# NEOS_Master-Slave.net
KiCad netlist of a schematic drawn in Altium Designer
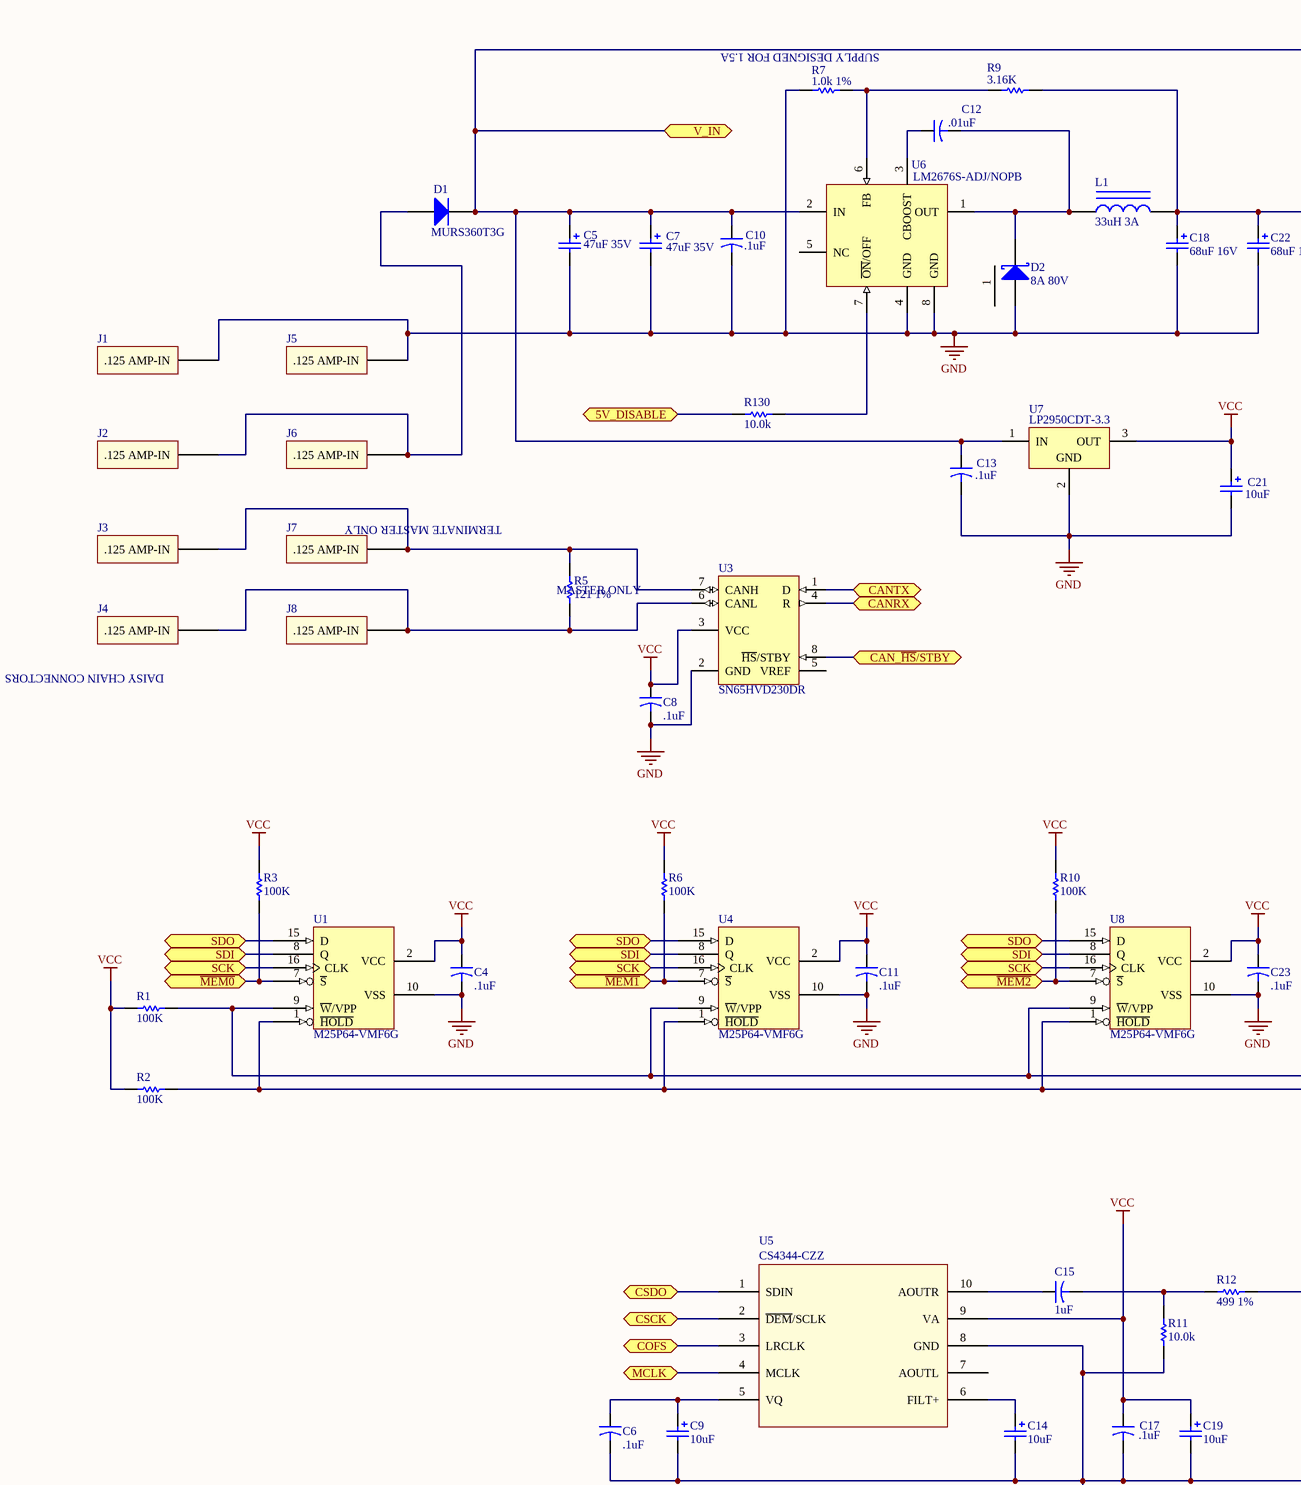
[diagram p0: NEOS Master-Slave.SchDoc, top left]
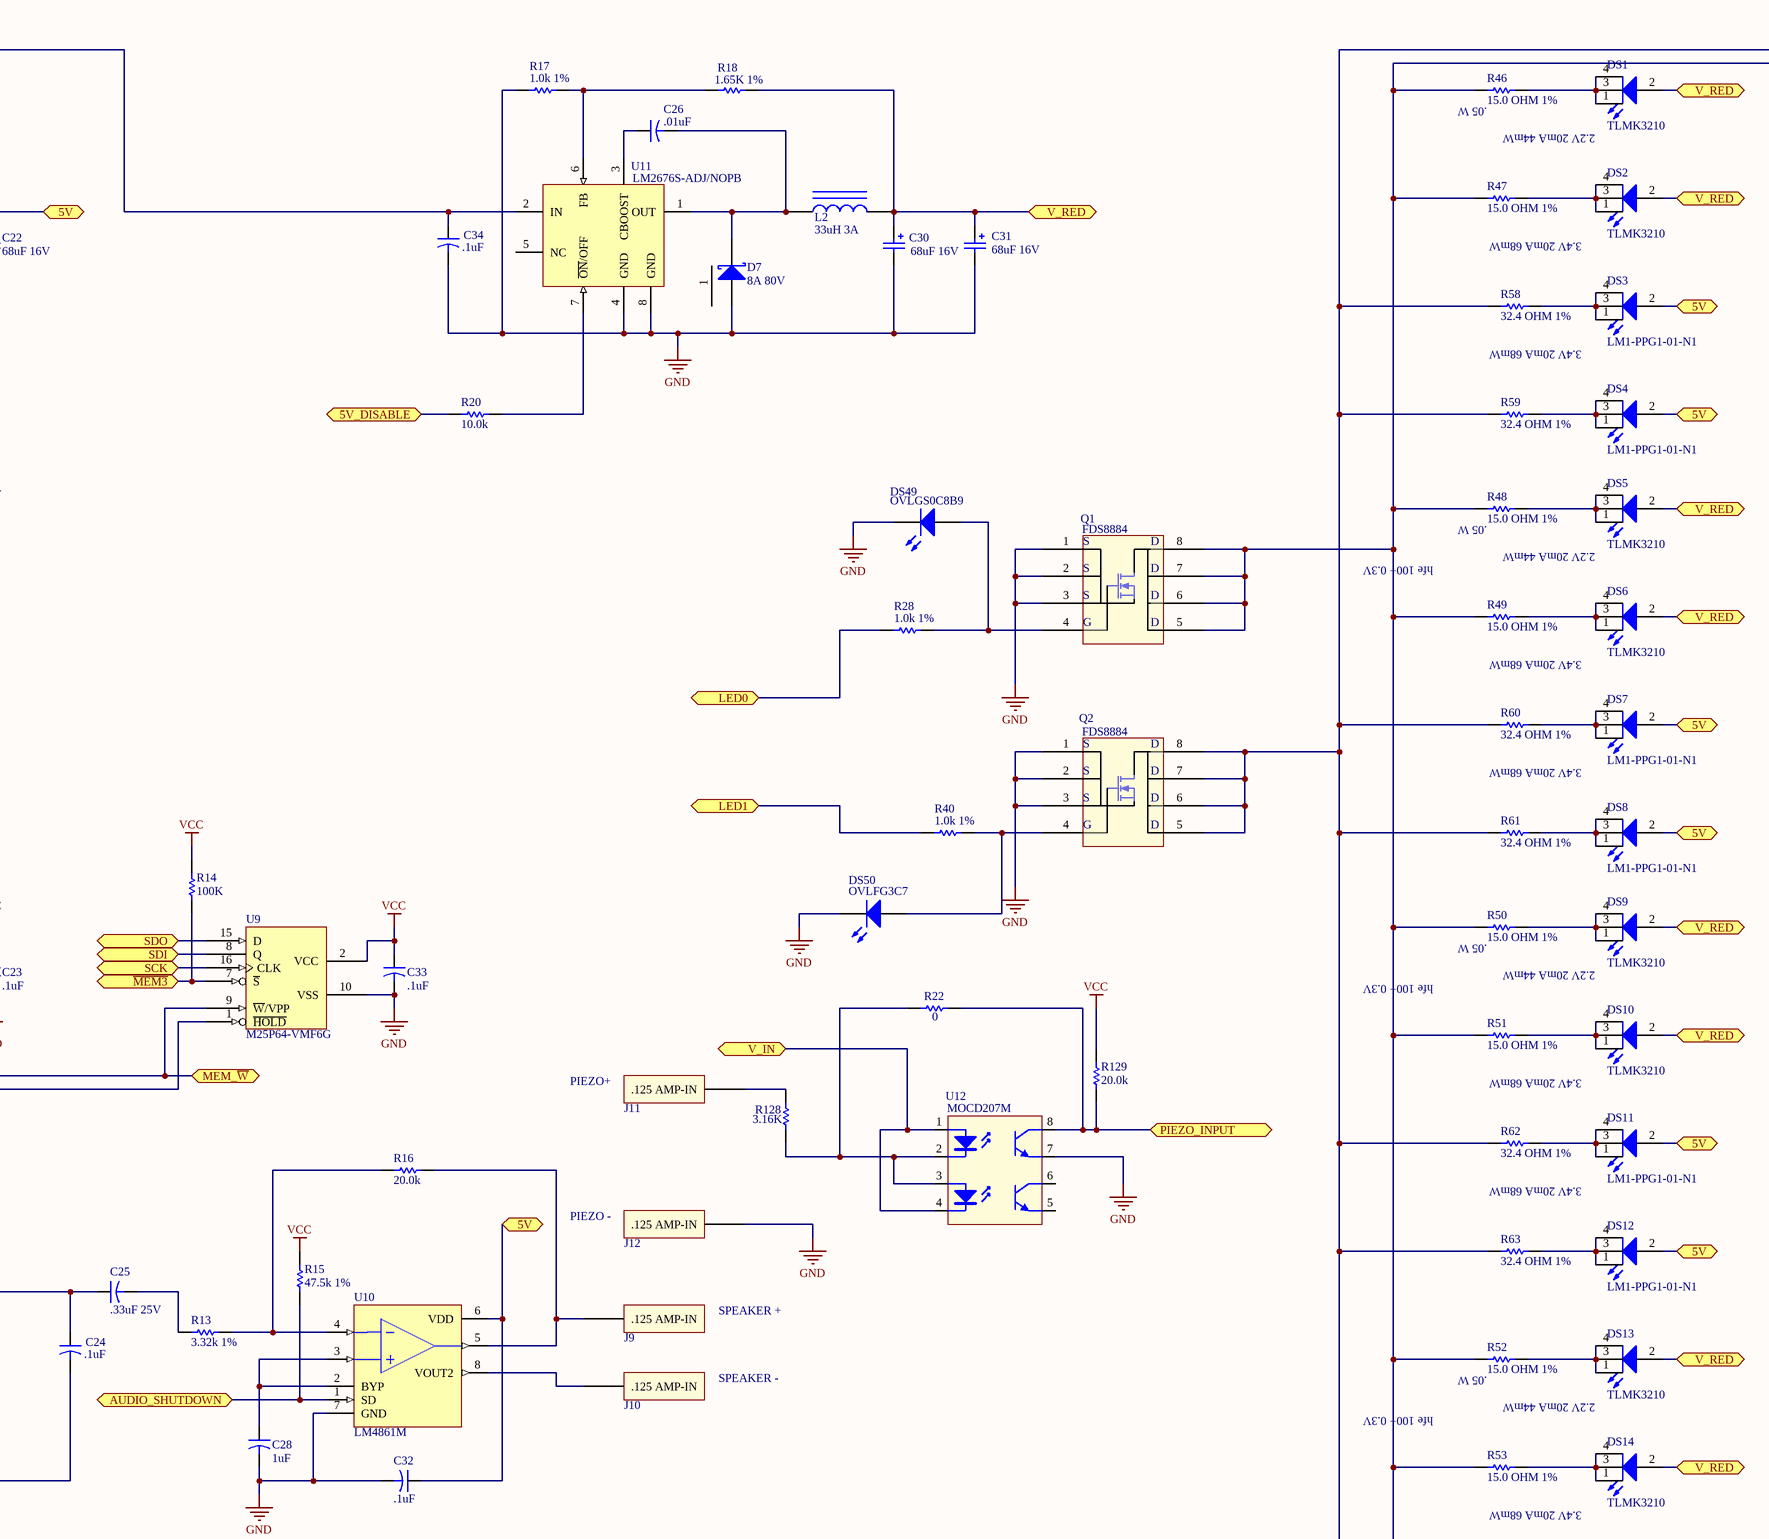
[diagram p1: NEOS Master-Slave.SchDoc, top middle]
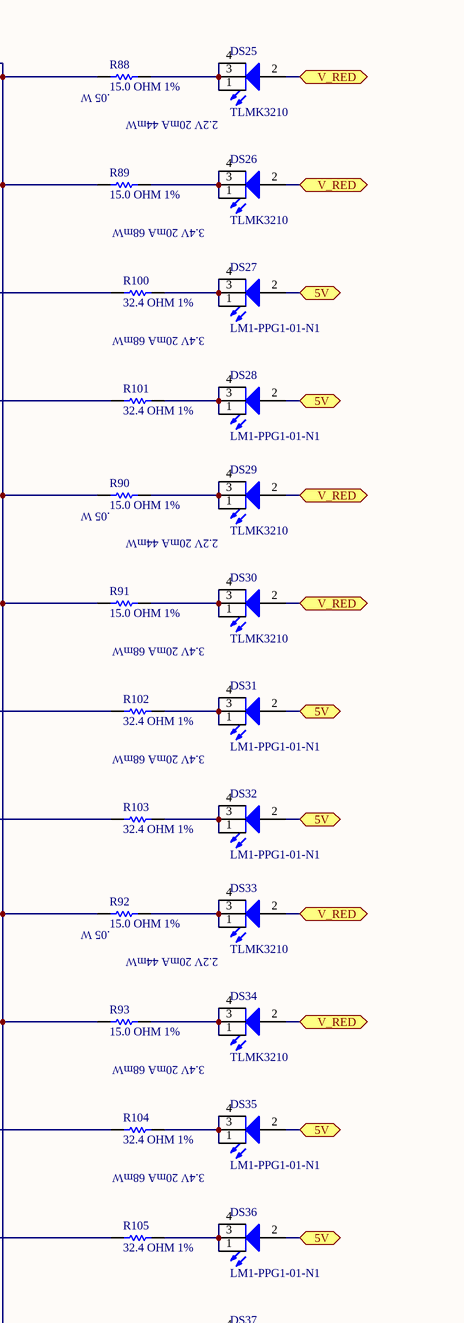
[diagram p2: NEOS Master-Slave.SchDoc, top right]
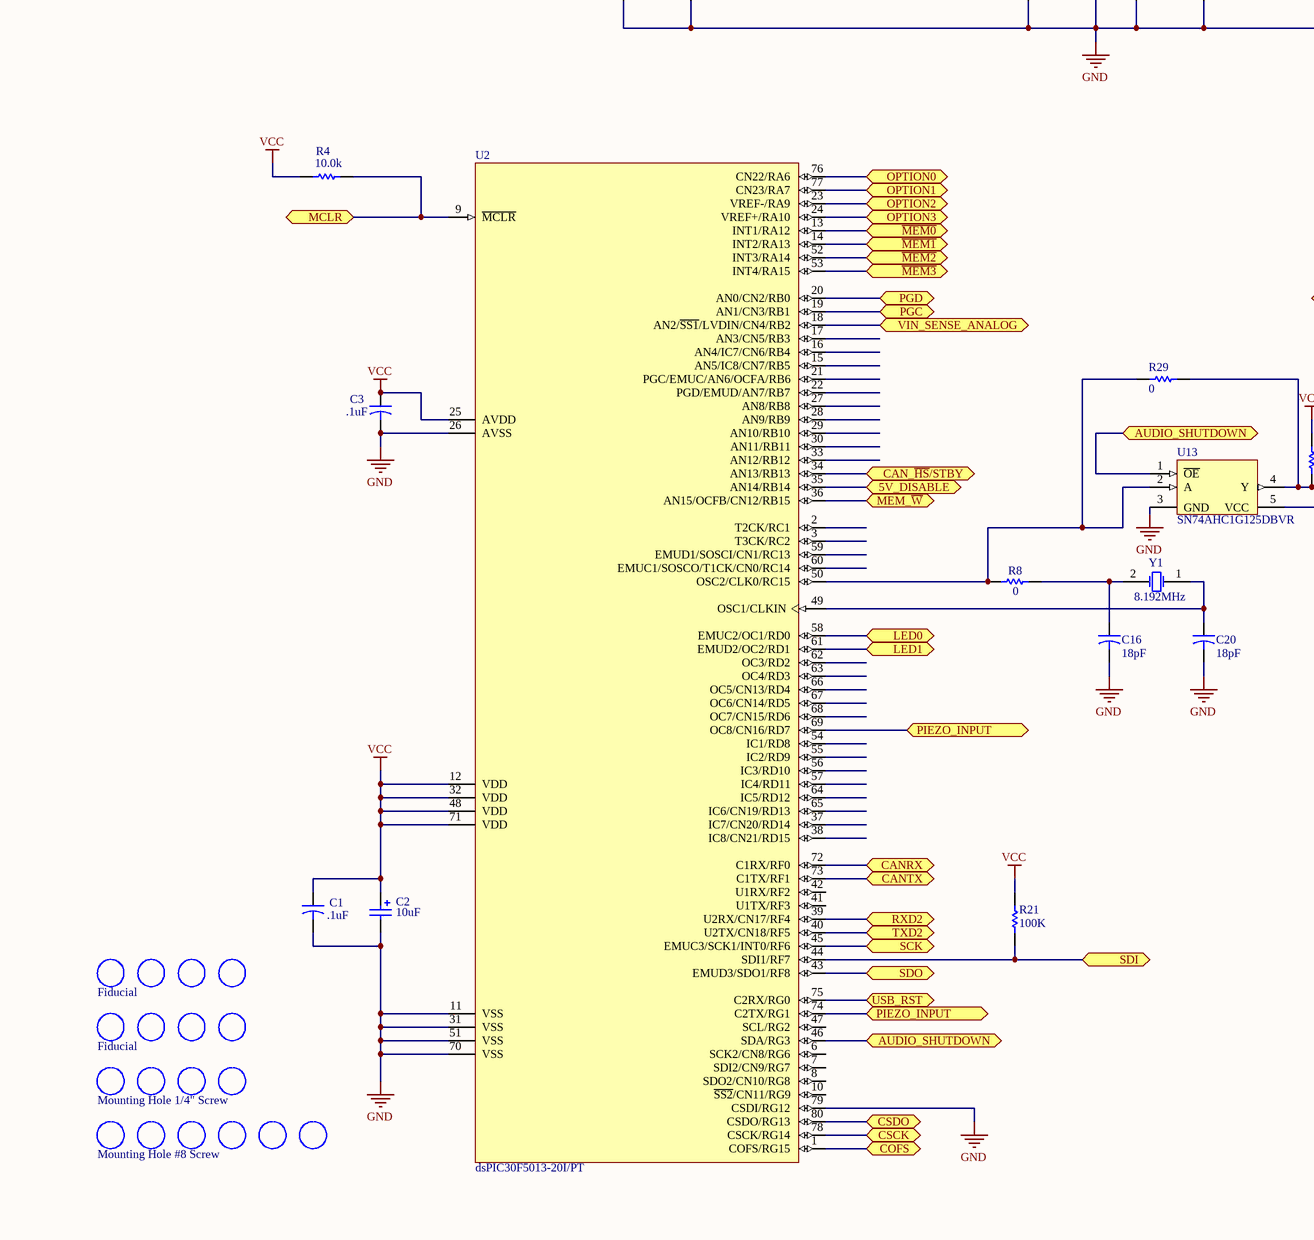
[diagram p3: NEOS Master-Slave.SchDoc, bottom left]
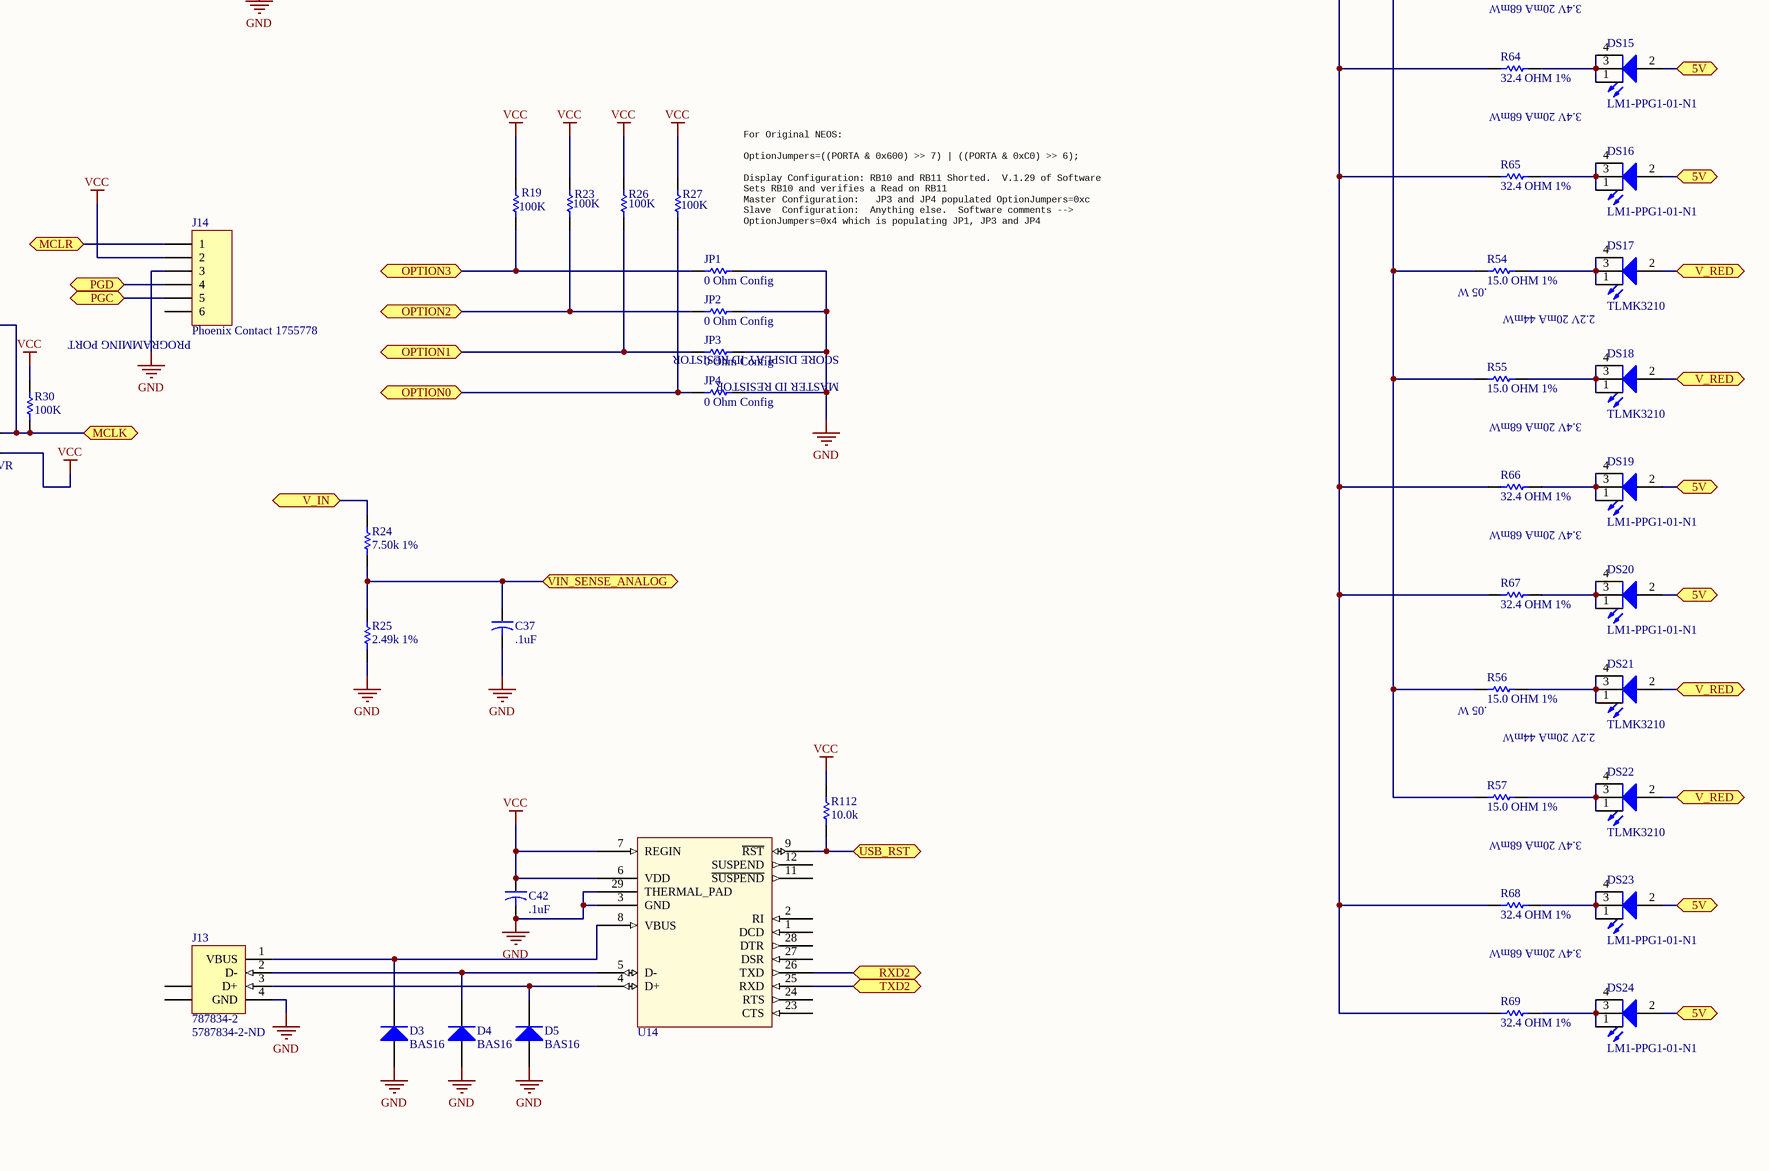
[diagram p4: NEOS Master-Slave.SchDoc, bottom middle]
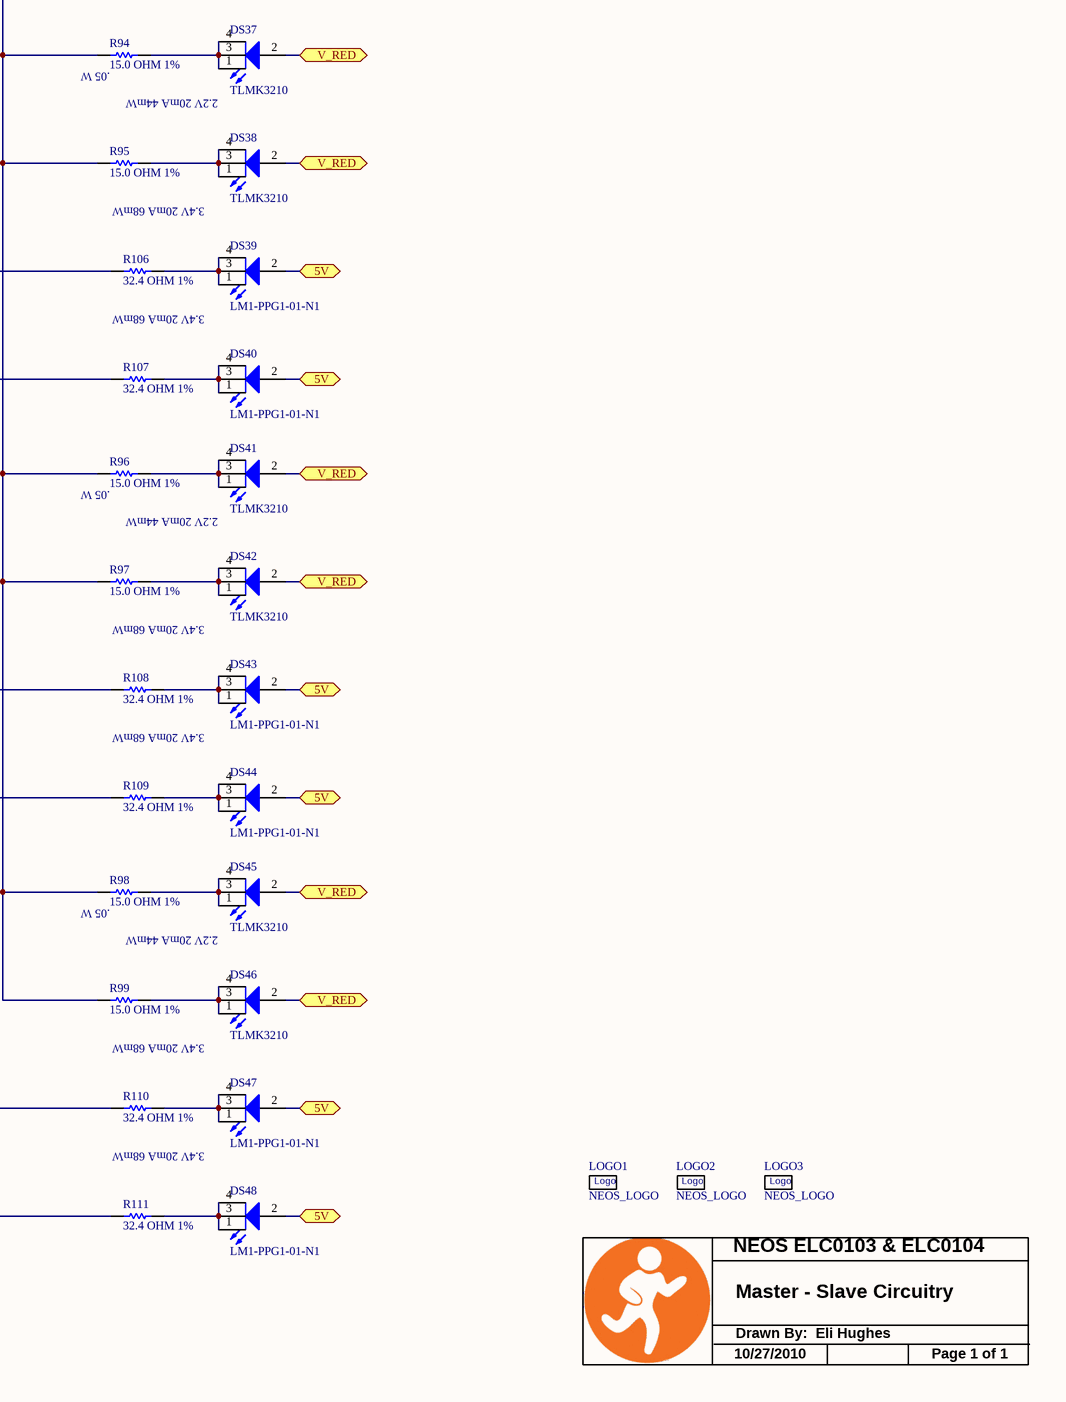
[diagram p5: NEOS Master-Slave.SchDoc, bottom right]

(export (version "E")
  (design (tool "Eeschema 10.0.6"))
  (components
    (comp (ref "C1")
      (value ".1uF")
      (footprint "C0805")
      (description "CAP .10UF 50V CERAMIC X7R 0805")
      (fields
        (field (name "MANUFACTURER") "Kemet")
        (field (name "MANUFACTURER PART NUMBER") "C0805C104K5RACTU")
      )
      (libsource (lib "API") (part "C#S/C0805C104K5RACK"))
    )
    (comp (ref "C2")
      (value "10uF")
      (footprint "API:C4X5.8")
      (description "CAP ELECT 10UF 16V FK SMD")
      (fields
        (field (name "MANUFACTURER") "Panasonic - ECG")
        (field (name "MANUFACTURER PART NUMBER") "EEE-FK1C100R")
      )
      (libsource (lib "API") (part "C#S/EEEFK1C100RP"))
    )
    (comp (ref "C3")
      (value ".1uF")
      (footprint "C0805")
      (description "CAP .10UF 50V CERAMIC X7R 0805")
      (fields
        (field (name "MANUFACTURER") "Kemet")
        (field (name "MANUFACTURER PART NUMBER") "C0805C104K5RACTU")
      )
      (libsource (lib "API") (part "C#S/C0805C104K5RACK"))
    )
    (comp (ref "C4")
      (value ".1uF")
      (footprint "C0805")
      (description "CAP .10UF 50V CERAMIC X7R 0805")
      (fields
        (field (name "MANUFACTURER") "Kemet")
        (field (name "MANUFACTURER PART NUMBER") "C0805C104K5RACTU")
      )
      (libsource (lib "") (part "C#S/C0805C104K5RACK_1"))
    )
    (comp (ref "C5")
      (value "47uF 35V")
      (footprint "C EIA7343-43 (X)")
      (description "CAPACITOR TANT 47UF 35V 10% SMD 7343-43 (EIA)")
      (fields
        (field (name "MANUFACTURER") "Kemet")
        (field (name "MANUFACTURER PART NUMBER") "T491X476K035AT")
      )
      (libsource (lib "API") (part "C#S/T491X476K035ATK"))
    )
    (comp (ref "C6")
      (value ".1uF")
      (footprint "C0805")
      (description "CAP .10UF 50V CERAMIC X7R 0805")
      (fields
        (field (name "MANUFACTURER") "Kemet")
        (field (name "MANUFACTURER PART NUMBER") "C0805C104K5RACTU")
      )
      (libsource (lib "") (part "C#S/C0805C104K5RACK_1"))
    )
    (comp (ref "C7")
      (value "47uF 35V")
      (footprint "C EIA7343-43 (X)")
      (description "CAPACITOR TANT 47UF 35V 10% SMD 7343-43 (EIA)")
      (fields
        (field (name "MANUFACTURER") "Kemet")
        (field (name "MANUFACTURER PART NUMBER") "T491X476K035AT")
      )
      (libsource (lib "API") (part "C#S/T491X476K035ATK"))
    )
    (comp (ref "C8")
      (value ".1uF")
      (footprint "C0805")
      (description "CAP .10UF 50V CERAMIC X7R 0805")
      (fields
        (field (name "MANUFACTURER") "Kemet")
        (field (name "MANUFACTURER PART NUMBER") "C0805C104K5RACTU")
      )
      (libsource (lib "") (part "C#S/C0805C104K5RACK_1"))
    )
    (comp (ref "C9")
      (value "10uF")
      (footprint "API:C4X5.8")
      (description "CAP ELECT 10UF 16V FK SMD")
      (fields
        (field (name "MANUFACTURER") "Panasonic - ECG")
        (field (name "MANUFACTURER PART NUMBER") "EEE-FK1C100R")
      )
      (libsource (lib "API") (part "C#S/EEEFK1C100RP"))
    )
    (comp (ref "C10")
      (value ".1uF")
      (footprint "C0805")
      (description "CAP .10UF 50V CERAMIC X7R 0805")
      (fields
        (field (name "MANUFACTURER") "Kemet")
        (field (name "MANUFACTURER PART NUMBER") "C0805C104K5RACTU")
      )
      (libsource (lib "") (part "C#S/C0805C104K5RACK_1"))
    )
    (comp (ref "C11")
      (value ".1uF")
      (footprint "C0805")
      (description "CAP .10UF 50V CERAMIC X7R 0805")
      (fields
        (field (name "MANUFACTURER") "Kemet")
        (field (name "MANUFACTURER PART NUMBER") "C0805C104K5RACTU")
      )
      (libsource (lib "") (part "C#S/C0805C104K5RACK_1"))
    )
    (comp (ref "C12")
      (value ".01uF")
      (footprint "API:C0805")
      (description "CAP 10000PF 50V CERAMIC X7R 0805")
      (fields
        (field (name "MANUFACTURER") "Kemet")
        (field (name "MANUFACTURER PART NUMBER") "C0805C103K5RACTU")
      )
      (libsource (lib "API") (part "C#S/C0805C103K5RAC"))
    )
    (comp (ref "C13")
      (value ".1uF")
      (footprint "C0805")
      (description "CAP .10UF 50V CERAMIC X7R 0805")
      (fields
        (field (name "MANUFACTURER") "Kemet")
        (field (name "MANUFACTURER PART NUMBER") "C0805C104K5RACTU")
      )
      (libsource (lib "") (part "C#S/C0805C104K5RACK_1"))
    )
    (comp (ref "C14")
      (value "10uF")
      (footprint "C4X5.8")
      (description "CAP ELECT 10UF 16V FK SMD")
      (fields
        (field (name "MANUFACTURER") "Panasonic - ECG")
        (field (name "MANUFACTURER PART NUMBER") "EEE-FK1C100R")
      )
      (libsource (lib "API") (part "C#S/EEEFK1C100RP"))
    )
    (comp (ref "C15")
      (value "1uF")
      (footprint "API:R1206")
      (description "CAP 1UF 25V CERAMIC X7R 1206")
      (fields
        (field (name "MANUFACTURER") "Panasonic - ECG")
        (field (name "MANUFACTURER PART NUMBER") "ECJ-3YB1E105K")
      )
      (libsource (lib "API") (part "C#S/ECJ3YB1E105KP"))
    )
    (comp (ref "C16")
      (value "18pF")
      (footprint "API:C0805")
      (description "CAP CERAMIC 18PF 50V NP0 0805")
      (fields
        (field (name "MANUFACTURER") "Kemet")
        (field (name "MANUFACTURER PART NUMBER") "C0805C180J5GACTU")
      )
      (libsource (lib "API") (part "C#S/C0805C180J5GACTUK"))
    )
    (comp (ref "C17")
      (value ".1uF")
      (footprint "C0805")
      (description "CAP .10UF 50V CERAMIC X7R 0805")
      (fields
        (field (name "MANUFACTURER") "Kemet")
        (field (name "MANUFACTURER PART NUMBER") "C0805C104K5RACTU")
      )
      (libsource (lib "") (part "C#S/C0805C104K5RACK_1"))
    )
    (comp (ref "C18")
      (value "68uF 16V")
      (footprint "API:C7343")
      (description "CAPACITOR TANT 68UF 16V 10% SMD")
      (fields
        (field (name "MANUFACTURER") "Kemet")
        (field (name "MANUFACTURER PART NUMBER") "T495D686K016ATE150")
      )
      (libsource (lib "API") (part "C#S/T495D686K016ATEK"))
    )
    (comp (ref "C19")
      (value "10uF")
      (footprint "API:C4X5.8")
      (description "CAP ELECT 10UF 16V FK SMD")
      (fields
        (field (name "MANUFACTURER") "Panasonic - ECG")
        (field (name "MANUFACTURER PART NUMBER") "EEE-FK1C100R")
      )
      (libsource (lib "API") (part "C#S/EEEFK1C100RP"))
    )
    (comp (ref "C20")
      (value "18pF")
      (footprint "API:C0805")
      (description "CAP CERAMIC 18PF 50V NP0 0805")
      (fields
        (field (name "MANUFACTURER") "Kemet")
        (field (name "MANUFACTURER PART NUMBER") "C0805C180J5GACTU")
      )
      (libsource (lib "API") (part "C#S/C0805C180J5GACTUK"))
    )
    (comp (ref "C21")
      (value "10uF")
      (footprint "API:C4X5.8")
      (description "CAP ELECT 10UF 16V FK SMD")
      (fields
        (field (name "MANUFACTURER") "Panasonic - ECG")
        (field (name "MANUFACTURER PART NUMBER") "EEE-FK1C100R")
      )
      (libsource (lib "API") (part "C#S/EEEFK1C100RP"))
    )
    (comp (ref "C22")
      (value "68uF 16V")
      (footprint "API:C7343")
      (description "CAPACITOR TANT 68UF 16V 10% SMD")
      (fields
        (field (name "MANUFACTURER") "Kemet")
        (field (name "MANUFACTURER PART NUMBER") "T495D686K016ATE150")
      )
      (libsource (lib "API") (part "C#S/T495D686K016ATEK"))
    )
    (comp (ref "C23")
      (value ".1uF")
      (footprint "C0805")
      (description "CAP .10UF 50V CERAMIC X7R 0805")
      (fields
        (field (name "MANUFACTURER") "Kemet")
        (field (name "MANUFACTURER PART NUMBER") "C0805C104K5RACTU")
      )
      (libsource (lib "") (part "C#S/C0805C104K5RACK_1"))
    )
    (comp (ref "C24")
      (value ".1uF")
      (footprint "C0805")
      (description "CAP .10UF 50V CERAMIC X7R 0805")
      (fields
        (field (name "MANUFACTURER") "Kemet")
        (field (name "MANUFACTURER PART NUMBER") "C0805C104K5RACTU")
      )
      (libsource (lib "") (part "C#S/C0805C104K5RACK_1"))
    )
    (comp (ref "C25")
      (value ".33uF 25V")
      (footprint "API:R1206")
      (description "CAP .33UF 25V CERAMIC X7R 1206")
      (fields
        (field (name "MANUFACTURER") "Panasonic - ECG")
        (field (name "MANUFACTURER PART NUMBER") "ECJ-3VB1E334K")
      )
      (libsource (lib "API") (part "C#S/ECJ3VB1E334KP"))
    )
    (comp (ref "C26")
      (value ".01uF")
      (footprint "API:C0805")
      (description "CAP 10000PF 50V CERAMIC X7R 0805")
      (fields
        (field (name "MANUFACTURER") "Kemet")
        (field (name "MANUFACTURER PART NUMBER") "C0805C103K5RACTU")
      )
      (libsource (lib "API") (part "C#S/C0805C103K5RAC"))
    )
    (comp (ref "C28")
      (value "1uF")
      (footprint "API:R1206")
      (description "CAP 1UF 25V CERAMIC X7R 1206")
      (fields
        (field (name "MANUFACTURER") "Panasonic - ECG")
        (field (name "MANUFACTURER PART NUMBER") "ECJ-3YB1E105K")
      )
      (libsource (lib "API") (part "C#S/ECJ3YB1E105KP"))
    )
    (comp (ref "C30")
      (value "68uF 16V")
      (footprint "C7343")
      (description "CAPACITOR TANT 68UF 16V 10% SMD")
      (fields
        (field (name "MANUFACTURER") "Kemet")
        (field (name "MANUFACTURER PART NUMBER") "T495D686K016ATE150")
      )
      (libsource (lib "API") (part "C#S/T495D686K016ATEK"))
    )
    (comp (ref "C31")
      (value "68uF 16V")
      (footprint "API:C7343")
      (description "CAPACITOR TANT 68UF 16V 10% SMD")
      (fields
        (field (name "MANUFACTURER") "Kemet")
        (field (name "MANUFACTURER PART NUMBER") "T495D686K016ATE150")
      )
      (libsource (lib "API") (part "C#S/T495D686K016ATEK"))
    )
    (comp (ref "C32")
      (value ".1uF")
      (footprint "C0805")
      (description "CAP .10UF 50V CERAMIC X7R 0805")
      (fields
        (field (name "MANUFACTURER") "Kemet")
        (field (name "MANUFACTURER PART NUMBER") "C0805C104K5RACTU")
      )
      (libsource (lib "") (part "C#S/C0805C104K5RACK_1"))
    )
    (comp (ref "C33")
      (value ".1uF")
      (footprint "C0805")
      (description "CAP .10UF 50V CERAMIC X7R 0805")
      (fields
        (field (name "MANUFACTURER") "Kemet")
        (field (name "MANUFACTURER PART NUMBER") "C0805C104K5RACTU")
      )
      (libsource (lib "") (part "C#S/C0805C104K5RACK_1"))
    )
    (comp (ref "C34")
      (value ".1uF")
      (footprint "C0805")
      (description "CAP .10UF 50V CERAMIC X7R 0805")
      (fields
        (field (name "MANUFACTURER") "Kemet")
        (field (name "MANUFACTURER PART NUMBER") "C0805C104K5RACTU")
      )
      (libsource (lib "") (part "C#S/C0805C104K5RACK_1"))
    )
    (comp (ref "C37")
      (value ".1uF")
      (footprint "C0805")
      (description "CAP .10UF 50V CERAMIC X7R 0805")
      (fields
        (field (name "MANUFACTURER") "Kemet")
        (field (name "MANUFACTURER PART NUMBER") "C0805C104K5RACTU")
      )
      (libsource (lib "") (part "C#S/C0805C104K5RACK_1"))
    )
    (comp (ref "C42")
      (value ".1uF")
      (footprint "C0805")
      (description "CAP .10UF 50V CERAMIC X7R 0805")
      (fields
        (field (name "MANUFACTURER") "Kemet")
        (field (name "MANUFACTURER PART NUMBER") "C0805C104K5RACTU")
      )
      (libsource (lib "") (part "C#S/C0805C104K5RACK_1"))
    )
    (comp (ref "D1")
      (value "DIODE ULTRA FAST 3A 600V SMC")
      (footprint "API:DIODE_SMC")
      (fields
        (field (name "MANUFACTURER") "ON Semiconductor")
        (field (name "MANUFACTURER PART NUMBER") "MURS360T3G")
      )
      (libsource (lib "API") (part "D#S/MURS360T3GM"))
    )
    (comp (ref "D2")
      (value "8A 80V")
      (footprint "API:D2PAK")
      (description "DIODE SCHOTTKY 80V 8A D2PAK")
      (fields
        (field (name "MANUFACTURER") "Vishay IR")
        (field (name "MANUFACTURER PART NUMBER") "8TQ100SPBF")
      )
      (libsource (lib "API") (part "D#S/8TQ080SPBFZ"))
    )
    (comp (ref "D3")
      (value "BAS16")
      (footprint "API:SOT23")
      (description "Diodes Inc BAS16 75V 200mA")
      (fields
        (field (name "MANUFACTURER") "Diodes Inc")
        (field (name "MANUFACTURER PART NUMBER") "BAS16-7-F")
      )
      (libsource (lib "API") (part "D#S/BAS167F0D"))
    )
    (comp (ref "D4")
      (value "BAS16")
      (footprint "API:SOT23")
      (description "Diodes Inc BAS16 75V 200mA")
      (fields
        (field (name "MANUFACTURER") "Diodes Inc")
        (field (name "MANUFACTURER PART NUMBER") "BAS16-7-F")
      )
      (libsource (lib "API") (part "D#S/BAS167F0D"))
    )
    (comp (ref "D5")
      (value "BAS16")
      (footprint "API:SOT23")
      (description "Diodes Inc BAS16 75V 200mA")
      (fields
        (field (name "MANUFACTURER") "Diodes Inc")
        (field (name "MANUFACTURER PART NUMBER") "BAS16-7-F")
      )
      (libsource (lib "API") (part "D#S/BAS167F0D"))
    )
    (comp (ref "D7")
      (value "8A 80V")
      (footprint "API:D2PAK")
      (description "DIODE SCHOTTKY 80V 8A D2PAK")
      (fields
        (field (name "MANUFACTURER") "Vishay IR")
        (field (name "MANUFACTURER PART NUMBER") "8TQ100SPBF")
      )
      (libsource (lib "API") (part "D#S/8TQ080SPBFZ"))
    )
    (comp (ref "DS1")
      (value "TLMK3210")
      (footprint "API:L#S/TLMK3210Z")
      (description "Vishay Red LED PLCC-3")
      (fields
        (field (name "MANUFACTURER") "Vishay")
        (field (name "MANUFACTURER PART NUMBER") "TLMK3210-GS08")
      )
      (libsource (lib "API") (part "L#S/TLMK3210"))
    )
    (comp (ref "DS2")
      (value "TLMK3210")
      (footprint "API:L#S/TLMK3210Z")
      (description "Vishay Red LED PLCC-3")
      (fields
        (field (name "MANUFACTURER") "Vishay")
        (field (name "MANUFACTURER PART NUMBER") "TLMK3210-GS08")
      )
      (libsource (lib "API") (part "L#S/TLMK3210"))
    )
    (comp (ref "DS3")
      (value "LM1-PPG1-01-N1")
      (footprint "L#S/TLMK3210Z")
      (description "120-degree, 3.3 x 3.5-mm, SMT LED in green color with water-transparent lens")
      (fields (field (name "MANUFACTURER") "Cree"))
      (libsource (lib "API") (part "L#S/LM1PPG103N1Z"))
    )
    (comp (ref "DS4")
      (value "LM1-PPG1-01-N1")
      (footprint "L#S/TLMK3210Z")
      (description "120-degree, 3.3 x 3.5-mm, SMT LED in green color with water-transparent lens")
      (fields (field (name "MANUFACTURER") "Cree"))
      (libsource (lib "API") (part "L#S/LM1PPG103N1Z"))
    )
    (comp (ref "DS5")
      (value "TLMK3210")
      (footprint "API:L#S/TLMK3210Z")
      (description "Vishay Red LED PLCC-3")
      (fields
        (field (name "MANUFACTURER") "Vishay")
        (field (name "MANUFACTURER PART NUMBER") "TLMK3210-GS08")
      )
      (libsource (lib "API") (part "L#S/TLMK3210"))
    )
    (comp (ref "DS6")
      (value "TLMK3210")
      (footprint "API:L#S/TLMK3210Z")
      (description "Vishay Red LED PLCC-3")
      (fields
        (field (name "MANUFACTURER") "Vishay")
        (field (name "MANUFACTURER PART NUMBER") "TLMK3210-GS08")
      )
      (libsource (lib "API") (part "L#S/TLMK3210"))
    )
    (comp (ref "DS7")
      (value "LM1-PPG1-01-N1")
      (footprint "L#S/TLMK3210Z")
      (description "120-degree, 3.3 x 3.5-mm, SMT LED in green color with water-transparent lens")
      (fields (field (name "MANUFACTURER") "Cree"))
      (libsource (lib "API") (part "L#S/LM1PPG103N1Z"))
    )
    (comp (ref "DS8")
      (value "LM1-PPG1-01-N1")
      (footprint "L#S/TLMK3210Z")
      (description "120-degree, 3.3 x 3.5-mm, SMT LED in green color with water-transparent lens")
      (fields (field (name "MANUFACTURER") "Cree"))
      (libsource (lib "API") (part "L#S/LM1PPG103N1Z"))
    )
    (comp (ref "DS9")
      (value "TLMK3210")
      (footprint "API:L#S/TLMK3210Z")
      (description "Vishay Red LED PLCC-3")
      (fields
        (field (name "MANUFACTURER") "Vishay")
        (field (name "MANUFACTURER PART NUMBER") "TLMK3210-GS08")
      )
      (libsource (lib "API") (part "L#S/TLMK3210"))
    )
    (comp (ref "DS10")
      (value "TLMK3210")
      (footprint "API:L#S/TLMK3210Z")
      (description "Vishay Red LED PLCC-3")
      (fields
        (field (name "MANUFACTURER") "Vishay")
        (field (name "MANUFACTURER PART NUMBER") "TLMK3210-GS08")
      )
      (libsource (lib "API") (part "L#S/TLMK3210"))
    )
    (comp (ref "DS11")
      (value "LM1-PPG1-01-N1")
      (footprint "L#S/TLMK3210Z")
      (description "120-degree, 3.3 x 3.5-mm, SMT LED in green color with water-transparent lens")
      (fields (field (name "MANUFACTURER") "Cree"))
      (libsource (lib "API") (part "L#S/LM1PPG103N1Z"))
    )
    (comp (ref "DS12")
      (value "LM1-PPG1-01-N1")
      (footprint "L#S/TLMK3210Z")
      (description "120-degree, 3.3 x 3.5-mm, SMT LED in green color with water-transparent lens")
      (fields (field (name "MANUFACTURER") "Cree"))
      (libsource (lib "API") (part "L#S/LM1PPG103N1Z"))
    )
    (comp (ref "DS13")
      (value "TLMK3210")
      (footprint "API:L#S/TLMK3210Z")
      (description "Vishay Red LED PLCC-3")
      (fields
        (field (name "MANUFACTURER") "Vishay")
        (field (name "MANUFACTURER PART NUMBER") "TLMK3210-GS08")
      )
      (libsource (lib "API") (part "L#S/TLMK3210"))
    )
    (comp (ref "DS14")
      (value "TLMK3210")
      (footprint "API:L#S/TLMK3210Z")
      (description "Vishay Red LED PLCC-3")
      (fields
        (field (name "MANUFACTURER") "Vishay")
        (field (name "MANUFACTURER PART NUMBER") "TLMK3210-GS08")
      )
      (libsource (lib "API") (part "L#S/TLMK3210"))
    )
    (comp (ref "DS15")
      (value "LM1-PPG1-01-N1")
      (footprint "L#S/TLMK3210Z")
      (description "120-degree, 3.3 x 3.5-mm, SMT LED in green color with water-transparent lens")
      (fields (field (name "MANUFACTURER") "Cree"))
      (libsource (lib "API") (part "L#S/LM1PPG103N1Z"))
    )
    (comp (ref "DS16")
      (value "LM1-PPG1-01-N1")
      (footprint "L#S/TLMK3210Z")
      (description "120-degree, 3.3 x 3.5-mm, SMT LED in green color with water-transparent lens")
      (fields (field (name "MANUFACTURER") "Cree"))
      (libsource (lib "API") (part "L#S/LM1PPG103N1Z"))
    )
    (comp (ref "DS17")
      (value "TLMK3210")
      (footprint "API:L#S/TLMK3210Z")
      (description "Vishay Red LED PLCC-3")
      (fields
        (field (name "MANUFACTURER") "Vishay")
        (field (name "MANUFACTURER PART NUMBER") "TLMK3210-GS08")
      )
      (libsource (lib "API") (part "L#S/TLMK3210"))
    )
    (comp (ref "DS18")
      (value "TLMK3210")
      (footprint "API:L#S/TLMK3210Z")
      (description "Vishay Red LED PLCC-3")
      (fields
        (field (name "MANUFACTURER") "Vishay")
        (field (name "MANUFACTURER PART NUMBER") "TLMK3210-GS08")
      )
      (libsource (lib "API") (part "L#S/TLMK3210"))
    )
    (comp (ref "DS19")
      (value "LM1-PPG1-01-N1")
      (footprint "L#S/TLMK3210Z")
      (description "120-degree, 3.3 x 3.5-mm, SMT LED in green color with water-transparent lens")
      (fields (field (name "MANUFACTURER") "Cree"))
      (libsource (lib "API") (part "L#S/LM1PPG103N1Z"))
    )
    (comp (ref "DS20")
      (value "LM1-PPG1-01-N1")
      (footprint "L#S/TLMK3210Z")
      (description "120-degree, 3.3 x 3.5-mm, SMT LED in green color with water-transparent lens")
      (fields (field (name "MANUFACTURER") "Cree"))
      (libsource (lib "API") (part "L#S/LM1PPG103N1Z"))
    )
    (comp (ref "DS21")
      (value "TLMK3210")
      (footprint "API:L#S/TLMK3210Z")
      (description "Vishay Red LED PLCC-3")
      (fields
        (field (name "MANUFACTURER") "Vishay")
        (field (name "MANUFACTURER PART NUMBER") "TLMK3210-GS08")
      )
      (libsource (lib "API") (part "L#S/TLMK3210"))
    )
    (comp (ref "DS22")
      (value "TLMK3210")
      (footprint "API:L#S/TLMK3210Z")
      (description "Vishay Red LED PLCC-3")
      (fields
        (field (name "MANUFACTURER") "Vishay")
        (field (name "MANUFACTURER PART NUMBER") "TLMK3210-GS08")
      )
      (libsource (lib "API") (part "L#S/TLMK3210"))
    )
    (comp (ref "DS23")
      (value "LM1-PPG1-01-N1")
      (footprint "L#S/TLMK3210Z")
      (description "120-degree, 3.3 x 3.5-mm, SMT LED in green color with water-transparent lens")
      (fields (field (name "MANUFACTURER") "Cree"))
      (libsource (lib "API") (part "L#S/LM1PPG103N1Z"))
    )
    (comp (ref "DS24")
      (value "LM1-PPG1-01-N1")
      (footprint "L#S/TLMK3210Z")
      (description "120-degree, 3.3 x 3.5-mm, SMT LED in green color with water-transparent lens")
      (fields (field (name "MANUFACTURER") "Cree"))
      (libsource (lib "API") (part "L#S/LM1PPG103N1Z"))
    )
    (comp (ref "DS25")
      (value "TLMK3210")
      (footprint "API:L#S/TLMK3210Z")
      (description "Vishay Red LED PLCC-3")
      (fields
        (field (name "MANUFACTURER") "Vishay")
        (field (name "MANUFACTURER PART NUMBER") "TLMK3210-GS08")
      )
      (libsource (lib "API") (part "L#S/TLMK3210"))
    )
    (comp (ref "DS26")
      (value "TLMK3210")
      (footprint "API:L#S/TLMK3210Z")
      (description "Vishay Red LED PLCC-3")
      (fields
        (field (name "MANUFACTURER") "Vishay")
        (field (name "MANUFACTURER PART NUMBER") "TLMK3210-GS08")
      )
      (libsource (lib "API") (part "L#S/TLMK3210"))
    )
    (comp (ref "DS27")
      (value "LM1-PPG1-01-N1")
      (footprint "L#S/TLMK3210Z")
      (description "120-degree, 3.3 x 3.5-mm, SMT LED in green color with water-transparent lens")
      (fields (field (name "MANUFACTURER") "Cree"))
      (libsource (lib "API") (part "L#S/LM1PPG103N1Z"))
    )
    (comp (ref "DS28")
      (value "LM1-PPG1-01-N1")
      (footprint "L#S/TLMK3210Z")
      (description "120-degree, 3.3 x 3.5-mm, SMT LED in green color with water-transparent lens")
      (fields (field (name "MANUFACTURER") "Cree"))
      (libsource (lib "API") (part "L#S/LM1PPG103N1Z"))
    )
    (comp (ref "DS29")
      (value "TLMK3210")
      (footprint "API:L#S/TLMK3210Z")
      (description "Vishay Red LED PLCC-3")
      (fields
        (field (name "MANUFACTURER") "Vishay")
        (field (name "MANUFACTURER PART NUMBER") "TLMK3210-GS08")
      )
      (libsource (lib "API") (part "L#S/TLMK3210"))
    )
    (comp (ref "DS30")
      (value "TLMK3210")
      (footprint "API:L#S/TLMK3210Z")
      (description "Vishay Red LED PLCC-3")
      (fields
        (field (name "MANUFACTURER") "Vishay")
        (field (name "MANUFACTURER PART NUMBER") "TLMK3210-GS08")
      )
      (libsource (lib "API") (part "L#S/TLMK3210"))
    )
    (comp (ref "DS31")
      (value "LM1-PPG1-01-N1")
      (footprint "L#S/TLMK3210Z")
      (description "120-degree, 3.3 x 3.5-mm, SMT LED in green color with water-transparent lens")
      (fields (field (name "MANUFACTURER") "Cree"))
      (libsource (lib "API") (part "L#S/LM1PPG103N1Z"))
    )
    (comp (ref "DS32")
      (value "LM1-PPG1-01-N1")
      (footprint "L#S/TLMK3210Z")
      (description "120-degree, 3.3 x 3.5-mm, SMT LED in green color with water-transparent lens")
      (fields (field (name "MANUFACTURER") "Cree"))
      (libsource (lib "API") (part "L#S/LM1PPG103N1Z"))
    )
    (comp (ref "DS33")
      (value "TLMK3210")
      (footprint "API:L#S/TLMK3210Z")
      (description "Vishay Red LED PLCC-3")
      (fields
        (field (name "MANUFACTURER") "Vishay")
        (field (name "MANUFACTURER PART NUMBER") "TLMK3210-GS08")
      )
      (libsource (lib "API") (part "L#S/TLMK3210"))
    )
    (comp (ref "DS34")
      (value "TLMK3210")
      (footprint "API:L#S/TLMK3210Z")
      (description "Vishay Red LED PLCC-3")
      (fields
        (field (name "MANUFACTURER") "Vishay")
        (field (name "MANUFACTURER PART NUMBER") "TLMK3210-GS08")
      )
      (libsource (lib "API") (part "L#S/TLMK3210"))
    )
    (comp (ref "DS35")
      (value "LM1-PPG1-01-N1")
      (footprint "L#S/TLMK3210Z")
      (description "120-degree, 3.3 x 3.5-mm, SMT LED in green color with water-transparent lens")
      (fields (field (name "MANUFACTURER") "Cree"))
      (libsource (lib "API") (part "L#S/LM1PPG103N1Z"))
    )
    (comp (ref "DS36")
      (value "LM1-PPG1-01-N1")
      (footprint "L#S/TLMK3210Z")
      (description "120-degree, 3.3 x 3.5-mm, SMT LED in green color with water-transparent lens")
      (fields (field (name "MANUFACTURER") "Cree"))
      (libsource (lib "API") (part "L#S/LM1PPG103N1Z"))
    )
    (comp (ref "DS37")
      (value "TLMK3210")
      (footprint "API:L#S/TLMK3210Z")
      (description "Vishay Red LED PLCC-3")
      (fields
        (field (name "MANUFACTURER") "Vishay")
        (field (name "MANUFACTURER PART NUMBER") "TLMK3210-GS08")
      )
      (libsource (lib "API") (part "L#S/TLMK3210"))
    )
    (comp (ref "DS38")
      (value "TLMK3210")
      (footprint "API:L#S/TLMK3210Z")
      (description "Vishay Red LED PLCC-3")
      (fields
        (field (name "MANUFACTURER") "Vishay")
        (field (name "MANUFACTURER PART NUMBER") "TLMK3210-GS08")
      )
      (libsource (lib "API") (part "L#S/TLMK3210"))
    )
    (comp (ref "DS39")
      (value "LM1-PPG1-01-N1")
      (footprint "L#S/TLMK3210Z")
      (description "120-degree, 3.3 x 3.5-mm, SMT LED in green color with water-transparent lens")
      (fields (field (name "MANUFACTURER") "Cree"))
      (libsource (lib "API") (part "L#S/LM1PPG103N1Z"))
    )
    (comp (ref "DS40")
      (value "LM1-PPG1-01-N1")
      (footprint "L#S/TLMK3210Z")
      (description "120-degree, 3.3 x 3.5-mm, SMT LED in green color with water-transparent lens")
      (fields (field (name "MANUFACTURER") "Cree"))
      (libsource (lib "API") (part "L#S/LM1PPG103N1Z"))
    )
    (comp (ref "DS41")
      (value "TLMK3210")
      (footprint "API:L#S/TLMK3210Z")
      (description "Vishay Red LED PLCC-3")
      (fields
        (field (name "MANUFACTURER") "Vishay")
        (field (name "MANUFACTURER PART NUMBER") "TLMK3210-GS08")
      )
      (libsource (lib "API") (part "L#S/TLMK3210"))
    )
    (comp (ref "DS42")
      (value "TLMK3210")
      (footprint "API:L#S/TLMK3210Z")
      (description "Vishay Red LED PLCC-3")
      (fields
        (field (name "MANUFACTURER") "Vishay")
        (field (name "MANUFACTURER PART NUMBER") "TLMK3210-GS08")
      )
      (libsource (lib "API") (part "L#S/TLMK3210"))
    )
    (comp (ref "DS43")
      (value "LM1-PPG1-01-N1")
      (footprint "L#S/TLMK3210Z")
      (description "120-degree, 3.3 x 3.5-mm, SMT LED in green color with water-transparent lens")
      (fields (field (name "MANUFACTURER") "Cree"))
      (libsource (lib "API") (part "L#S/LM1PPG103N1Z"))
    )
    (comp (ref "DS44")
      (value "LM1-PPG1-01-N1")
      (footprint "L#S/TLMK3210Z")
      (description "120-degree, 3.3 x 3.5-mm, SMT LED in green color with water-transparent lens")
      (fields (field (name "MANUFACTURER") "Cree"))
      (libsource (lib "API") (part "L#S/LM1PPG103N1Z"))
    )
    (comp (ref "DS45")
      (value "TLMK3210")
      (footprint "API:L#S/TLMK3210Z")
      (description "Vishay Red LED PLCC-3")
      (fields
        (field (name "MANUFACTURER") "Vishay")
        (field (name "MANUFACTURER PART NUMBER") "TLMK3210-GS08")
      )
      (libsource (lib "API") (part "L#S/TLMK3210"))
    )
    (comp (ref "DS46")
      (value "TLMK3210")
      (footprint "API:L#S/TLMK3210Z")
      (description "Vishay Red LED PLCC-3")
      (fields
        (field (name "MANUFACTURER") "Vishay")
        (field (name "MANUFACTURER PART NUMBER") "TLMK3210-GS08")
      )
      (libsource (lib "API") (part "L#S/TLMK3210"))
    )
    (comp (ref "DS47")
      (value "LM1-PPG1-01-N1")
      (footprint "L#S/TLMK3210Z")
      (description "120-degree, 3.3 x 3.5-mm, SMT LED in green color with water-transparent lens")
      (fields (field (name "MANUFACTURER") "Cree"))
      (libsource (lib "API") (part "L#S/LM1PPG103N1Z"))
    )
    (comp (ref "DS48")
      (value "LM1-PPG1-01-N1")
      (footprint "L#S/TLMK3210Z")
      (description "120-degree, 3.3 x 3.5-mm, SMT LED in green color with water-transparent lens")
      (fields (field (name "MANUFACTURER") "Cree"))
      (libsource (lib "API") (part "L#S/LM1PPG103N1Z"))
    )
    (comp (ref "DS49")
      (value "OVLGS0C8B9")
      (footprint "LED T1-3/4 Flush")
      (description "LED 631NM TAPERED RED 5MM")
      (fields (field (name "MANUFACTURER") "TT Electronics/Optek Technology"))
      (libsource (lib "API") (part "LRCOVLFR3C7Z"))
    )
    (comp (ref "DS50")
      (value "OVLFG3C7")
      (footprint "LED T1-3/4 Flush")
      (description "LED 525NM ROUND GREEN 5MM")
      (fields (field (name "MANUFACTURER") "TT Electronics/Optek Technology"))
      (libsource (lib "API") (part "LGCOVLFG3C7Z"))
    )
    (comp (ref "FID1")
      (value "Fiducial")
      (footprint "Fiducial")
      (fields
        (field (name "MANUFACTURER") "Manufacturer")
        (field (name "MANUFACTURER PART NUMBER") "Manufacturer Part Number")
      )
      (libsource (lib "API") (part "Fiducial"))
    )
    (comp (ref "FID2")
      (value "Fiducial")
      (footprint "Fiducial")
      (fields
        (field (name "MANUFACTURER") "Manufacturer")
        (field (name "MANUFACTURER PART NUMBER") "Manufacturer Part Number")
      )
      (libsource (lib "API") (part "Fiducial"))
    )
    (comp (ref "FID3")
      (value "Fiducial")
      (footprint "Fiducial")
      (fields
        (field (name "MANUFACTURER") "Manufacturer")
        (field (name "MANUFACTURER PART NUMBER") "Manufacturer Part Number")
      )
      (libsource (lib "API") (part "Fiducial"))
    )
    (comp (ref "FID4")
      (value "Fiducial")
      (footprint "Fiducial")
      (fields
        (field (name "MANUFACTURER") "Manufacturer")
        (field (name "MANUFACTURER PART NUMBER") "Manufacturer Part Number")
      )
      (libsource (lib "API") (part "Fiducial"))
    )
    (comp (ref "FID5")
      (value "Fiducial")
      (footprint "Fiducial")
      (fields
        (field (name "MANUFACTURER") "Manufacturer")
        (field (name "MANUFACTURER PART NUMBER") "Manufacturer Part Number")
      )
      (libsource (lib "API") (part "Fiducial"))
    )
    (comp (ref "FID6")
      (value "Fiducial")
      (footprint "Fiducial")
      (fields
        (field (name "MANUFACTURER") "Manufacturer")
        (field (name "MANUFACTURER PART NUMBER") "Manufacturer Part Number")
      )
      (libsource (lib "API") (part "Fiducial"))
    )
    (comp (ref "FID7")
      (value "Fiducial")
      (footprint "Fiducial")
      (fields
        (field (name "MANUFACTURER") "Manufacturer")
        (field (name "MANUFACTURER PART NUMBER") "Manufacturer Part Number")
      )
      (libsource (lib "API") (part "Fiducial"))
    )
    (comp (ref "FID8")
      (value "Fiducial")
      (footprint "Fiducial")
      (fields
        (field (name "MANUFACTURER") "Manufacturer")
        (field (name "MANUFACTURER PART NUMBER") "Manufacturer Part Number")
      )
      (libsource (lib "API") (part "Fiducial"))
    )
    (comp (ref "J1")
      (value "*")
      (footprint "API:WIRE_125")
      (fields
        (field (name "MANUFACTURER") "Manufacturer")
        (field (name "MANUFACTURER PART NUMBER") "Manufacturer Part Number")
      )
      (libsource (lib "API") (part "~125_WIRE"))
    )
    (comp (ref "J2")
      (value "*")
      (footprint "API:WIRE_125")
      (fields
        (field (name "MANUFACTURER") "Manufacturer")
        (field (name "MANUFACTURER PART NUMBER") "Manufacturer Part Number")
      )
      (libsource (lib "API") (part "~125_WIRE"))
    )
    (comp (ref "J3")
      (value "*")
      (footprint "API:WIRE_125")
      (fields
        (field (name "MANUFACTURER") "Manufacturer")
        (field (name "MANUFACTURER PART NUMBER") "Manufacturer Part Number")
      )
      (libsource (lib "API") (part "~125_WIRE"))
    )
    (comp (ref "J4")
      (value "*")
      (footprint "API:WIRE_125")
      (fields
        (field (name "MANUFACTURER") "Manufacturer")
        (field (name "MANUFACTURER PART NUMBER") "Manufacturer Part Number")
      )
      (libsource (lib "API") (part "~125_WIRE"))
    )
    (comp (ref "J5")
      (value "*")
      (footprint "API:WIRE_125")
      (fields
        (field (name "MANUFACTURER") "Manufacturer")
        (field (name "MANUFACTURER PART NUMBER") "Manufacturer Part Number")
      )
      (libsource (lib "API") (part "~125_WIRE"))
    )
    (comp (ref "J6")
      (value "*")
      (footprint "API:WIRE_125")
      (fields
        (field (name "MANUFACTURER") "Manufacturer")
        (field (name "MANUFACTURER PART NUMBER") "Manufacturer Part Number")
      )
      (libsource (lib "API") (part "~125_WIRE"))
    )
    (comp (ref "J7")
      (value "*")
      (footprint "API:WIRE_125")
      (fields
        (field (name "MANUFACTURER") "Manufacturer")
        (field (name "MANUFACTURER PART NUMBER") "Manufacturer Part Number")
      )
      (libsource (lib "API") (part "~125_WIRE"))
    )
    (comp (ref "J8")
      (value "*")
      (footprint "API:WIRE_125")
      (fields
        (field (name "MANUFACTURER") "Manufacturer")
        (field (name "MANUFACTURER PART NUMBER") "Manufacturer Part Number")
      )
      (libsource (lib "API") (part "~125_WIRE"))
    )
    (comp (ref "J9")
      (value "*")
      (footprint "API:WIRE_125")
      (fields
        (field (name "MANUFACTURER") "Manufacturer")
        (field (name "MANUFACTURER PART NUMBER") "Manufacturer Part Number")
      )
      (libsource (lib "") (part "~125_WIRE_1"))
    )
    (comp (ref "J10")
      (value "*")
      (footprint "API:WIRE_125")
      (fields
        (field (name "MANUFACTURER") "Manufacturer")
        (field (name "MANUFACTURER PART NUMBER") "Manufacturer Part Number")
      )
      (libsource (lib "") (part "~125_WIRE_1"))
    )
    (comp (ref "J11")
      (value "*")
      (footprint "API:WIRE_125")
      (fields
        (field (name "MANUFACTURER") "Manufacturer")
        (field (name "MANUFACTURER PART NUMBER") "Manufacturer Part Number")
      )
      (libsource (lib "API") (part "~125_WIRE"))
    )
    (comp (ref "J12")
      (value "*")
      (footprint "API:WIRE_125")
      (fields
        (field (name "MANUFACTURER") "Manufacturer")
        (field (name "MANUFACTURER PART NUMBER") "Manufacturer Part Number")
      )
      (libsource (lib "API") (part "~125_WIRE"))
    )
    (comp (ref "J13")
      (value "787834-2")
      (footprint "KUSBVX-BS1N")
      (description "USB 1.1, Vertical, Thru-Hole, B Type, Receptacle, 4 Position, Natural")
      (fields
        (field (name "MANUFACTURER") "Tyco Electronics")
        (field (name "MANUFACTURER PART NUMBER") "5787834-2")
        (field (name "SUPPLIER PART NUMBER 1") "5787834-2-ND")
        (field (name "PUBLISHER") "Altium Limited")
      )
      (libsource (lib "ScoreBoard") (part "787834-2"))
    )
    (comp (ref "J14")
      (value "Phoenix Contact 1755778")
      (footprint "JCPM5086VE0Z")
      (description "CONN HEADER VERT 6POS 5.08MM")
      (fields
        (field (name "MANUFACTURER") "Phoenix Contact")
        (field (name "MANUFACTURER PART NUMBER") "1755778")
      )
      (libsource (lib "API") (part "JCPM5086VE0Z"))
    )
    (comp (ref "JP1")
      (value "0 Ohm Config")
      (description "RES 0.0 OHM 1/8W 5% 0805 SMD")
      (fields
        (field (name "MANUFACTURER") "Panasonic - ECG")
        (field (name "MANUFACTURER PART NUMBER") "ERJ-6GEY0R00V")
      )
      (libsource (lib "API") (part "RS/ERJ6ENF"))
    )
    (comp (ref "JP2")
      (value "0 Ohm Config")
      (description "RES 0.0 OHM 1/8W 5% 0805 SMD")
      (fields
        (field (name "MANUFACTURER") "Panasonic - ECG")
        (field (name "MANUFACTURER PART NUMBER") "ERJ-6GEY0R00V")
      )
      (libsource (lib "API") (part "RS/ERJ6ENF"))
    )
    (comp (ref "JP3")
      (value "0 Ohm Config")
      (description "RES 0.0 OHM 1/8W 5% 0805 SMD")
      (fields
        (field (name "MANUFACTURER") "Panasonic - ECG")
        (field (name "MANUFACTURER PART NUMBER") "ERJ-6GEY0R00V")
      )
      (libsource (lib "API") (part "RS/ERJ6ENF"))
    )
    (comp (ref "JP4")
      (value "0 Ohm Config")
      (footprint "0805")
      (description "RES 0.0 OHM 1/8W 5% 0805 SMD")
      (fields
        (field (name "MANUFACTURER") "Panasonic - ECG")
        (field (name "MANUFACTURER PART NUMBER") "ERJ-6GEY0R00V")
      )
      (libsource (lib "API") (part "RS/ERJ6ENF"))
    )
    (comp (ref "L1")
      (value "33uH 3A")
      (footprint "API:IND/DO5022")
      (description "33uH 3A Surface Mount Inductor")
      (fields
        (field (name "MANUFACTURER") "CoilCraft")
        (field (name "MANUFACTURER PART NUMBER") "DO5022P-333MLB")
      )
      (libsource (lib "API") (part "N#S/DO5022P333Z"))
    )
    (comp (ref "L2")
      (value "33uH 3A")
      (footprint "API:IND/DO5022")
      (description "33uH 3A Surface Mount Inductor")
      (fields
        (field (name "MANUFACTURER") "CoilCraft")
        (field (name "MANUFACTURER PART NUMBER") "DO5022P-333MLB")
      )
      (libsource (lib "API") (part "N#S/DO5022P333Z"))
    )
    (comp (ref "LOGO1")
      (value "NEOS_LOGO")
      (footprint "NEOS_LOGO_0")
      (libsource (lib "eLogo") (part "NEOS_LOGO"))
    )
    (comp (ref "LOGO2")
      (value "NEOS_LOGO")
      (footprint "FULL_LOGO")
      (libsource (lib "eLogo") (part "NEOS_LOGO"))
    )
    (comp (ref "LOGO3")
      (value "NEOS_LOGO")
      (footprint "NEOS_LOGO_0")
      (libsource (lib "eLogo") (part "NEOS_LOGO"))
    )
    (comp (ref "M1")
      (value "Mounting Hole 1/4\" Screw")
      (footprint "MHole250")
      (fields
        (field (name "MANUFACTURER") "Manufacturer")
        (field (name "MANUFACTURER PART NUMBER") "Manufacturer Part Number")
      )
      (libsource (lib "Rays_Altium") (part "MountingHole_1/4"))
    )
    (comp (ref "M2")
      (value "Mounting Hole 1/4\" Screw")
      (footprint "MHole250")
      (fields
        (field (name "MANUFACTURER") "Manufacturer")
        (field (name "MANUFACTURER PART NUMBER") "Manufacturer Part Number")
      )
      (libsource (lib "Rays_Altium") (part "MountingHole_1/4"))
    )
    (comp (ref "M3")
      (value "Mounting Hole 1/4\" Screw")
      (footprint "MHole250")
      (fields
        (field (name "MANUFACTURER") "Manufacturer")
        (field (name "MANUFACTURER PART NUMBER") "Manufacturer Part Number")
      )
      (libsource (lib "Rays_Altium") (part "MountingHole_1/4"))
    )
    (comp (ref "M4")
      (value "Mounting Hole 1/4\" Screw")
      (footprint "MHole250")
      (fields
        (field (name "MANUFACTURER") "Manufacturer")
        (field (name "MANUFACTURER PART NUMBER") "Manufacturer Part Number")
      )
      (libsource (lib "Rays_Altium") (part "MountingHole_1/4"))
    )
    (comp (ref "M5")
      (value "Mounting Hole #8 Screw")
      (footprint "MHole#8")
      (fields
        (field (name "MANUFACTURER") "Manufacturer")
        (field (name "MANUFACTURER PART NUMBER") "Manufacturer Part Number")
      )
      (libsource (lib "Rays_Altium") (part "MountingHole_8"))
    )
    (comp (ref "M6")
      (value "Mounting Hole #8 Screw")
      (footprint "MHole#8")
      (fields
        (field (name "MANUFACTURER") "Manufacturer")
        (field (name "MANUFACTURER PART NUMBER") "Manufacturer Part Number")
      )
      (libsource (lib "Rays_Altium") (part "MountingHole_8"))
    )
    (comp (ref "M7")
      (value "Mounting Hole #8 Screw")
      (footprint "MHole#8")
      (fields
        (field (name "MANUFACTURER") "Manufacturer")
        (field (name "MANUFACTURER PART NUMBER") "Manufacturer Part Number")
      )
      (libsource (lib "Rays_Altium") (part "MountingHole_8"))
    )
    (comp (ref "M8")
      (value "Mounting Hole #8 Screw")
      (footprint "MHole#8")
      (fields
        (field (name "MANUFACTURER") "Manufacturer")
        (field (name "MANUFACTURER PART NUMBER") "Manufacturer Part Number")
      )
      (libsource (lib "Rays_Altium") (part "MountingHole_8"))
    )
    (comp (ref "M9")
      (value "Mounting Hole #8 Screw")
      (footprint "MHole#8")
      (fields
        (field (name "MANUFACTURER") "Manufacturer")
        (field (name "MANUFACTURER PART NUMBER") "Manufacturer Part Number")
      )
      (libsource (lib "Rays_Altium") (part "MountingHole_8"))
    )
    (comp (ref "M10")
      (value "Mounting Hole #8 Screw")
      (footprint "MHole#8")
      (fields
        (field (name "MANUFACTURER") "Manufacturer")
        (field (name "MANUFACTURER PART NUMBER") "Manufacturer Part Number")
      )
      (libsource (lib "Rays_Altium") (part "MountingHole_8"))
    )
    (comp (ref "Q1")
      (value "FDS8884")
      (footprint "SO8")
      (description "MOSFET N-CH 30V 8.5A 8-SOIC")
      (fields (field (name "MANUFACTURER") "Fairchild Semiconductor"))
      (libsource (lib "API") (part "Q#S/FDS8884F"))
    )
    (comp (ref "Q2")
      (value "FDS8884")
      (footprint "SO8")
      (description "MOSFET N-CH 30V 8.5A 8-SOIC")
      (fields (field (name "MANUFACTURER") "Fairchild Semiconductor"))
      (libsource (lib "API") (part "Q#S/FDS8884F"))
    )
    (comp (ref "R1")
      (value "100K")
      (footprint "R0805")
      (description "RES 100K OHM 1/8W 1% 0805 SMD")
      (fields
        (field (name "MANUFACTURER") "Panasonic - ECG")
        (field (name "MANUFACTURER PART NUMBER") "RC0805JR-07100KL")
      )
      (libsource (lib "API") (part "RS/ERJ6ENF"))
    )
    (comp (ref "R2")
      (value "100K")
      (footprint "R0805")
      (description "RES 100K OHM 1/8W 1% 0805 SMD")
      (fields
        (field (name "MANUFACTURER") "Panasonic - ECG")
        (field (name "MANUFACTURER PART NUMBER") "RC0805JR-07100KL")
      )
      (libsource (lib "API") (part "RS/ERJ6ENF"))
    )
    (comp (ref "R3")
      (value "100K")
      (footprint "R0805")
      (description "RES 100K OHM 1/8W 1% 0805 SMD")
      (fields
        (field (name "MANUFACTURER") "Panasonic - ECG")
        (field (name "MANUFACTURER PART NUMBER") "RC0805JR-07100KL")
      )
      (libsource (lib "API") (part "RS/ERJ6ENF"))
    )
    (comp (ref "R4")
      (value "10.0k")
      (footprint "R0805")
      (description "RES 10.0K OHM 1/8W 1% 0805 SMD")
      (fields
        (field (name "MANUFACTURER") "Panasonic - ECG")
        (field (name "MANUFACTURER PART NUMBER") "ERJ-6ENF1002V")
      )
      (libsource (lib "API") (part "RS/ERJ6ENF"))
    )
    (comp (ref "R5")
      (value "121 1%")
      (footprint "R1206")
      (description "RES 121 OHM 1/4W 1% 1206 SMD")
      (fields
        (field (name "MANUFACTURER") "Panasonic - ECG")
        (field (name "MANUFACTURER PART NUMBER") "ERJ-8ENF1210V")
      )
      (libsource (lib "API") (part "RS/ERJ8ENF"))
    )
    (comp (ref "R6")
      (value "100K")
      (footprint "R0805")
      (description "RES 100K OHM 1/8W 1% 0805 SMD")
      (fields
        (field (name "MANUFACTURER") "Panasonic - ECG")
        (field (name "MANUFACTURER PART NUMBER") "RC0805JR-07100KL")
      )
      (libsource (lib "API") (part "RS/ERJ6ENF"))
    )
    (comp (ref "R7")
      (value "1.0k 1%")
      (footprint "R0805")
      (description "RES 1.00K OHM 1/8W 1% 0805 SMD")
      (fields
        (field (name "MANUFACTURER") "Yageo")
        (field (name "MANUFACTURER PART NUMBER") "RC0805FR-071KL")
      )
      (libsource (lib "API") (part "RS/ERJ6ENF"))
    )
    (comp (ref "R8")
      (value "0")
      (footprint "R0805")
      (description "RES 0.0 OHM 1/8W 5% 0805 SMD")
      (fields
        (field (name "MANUFACTURER") "Panasonic - ECG")
        (field (name "MANUFACTURER PART NUMBER") "ERJ-6GEY0R00V")
      )
      (libsource (lib "API") (part "RS/ERJ6GEYJ"))
    )
    (comp (ref "R9")
      (value "3.16K")
      (footprint "R0805")
      (description "RES 3.16K OHM 1/8W 1% 0805 SMD")
      (fields
        (field (name "MANUFACTURER") "Panasonic - ECG")
        (field (name "MANUFACTURER PART NUMBER") "ERJ-6ENF3161V")
      )
      (libsource (lib "API") (part "RS/ERJ6ENF"))
    )
    (comp (ref "R10")
      (value "100K")
      (footprint "R0805")
      (description "RES 100K OHM 1/8W 1% 0805 SMD")
      (fields
        (field (name "MANUFACTURER") "Panasonic - ECG")
        (field (name "MANUFACTURER PART NUMBER") "RC0805JR-07100KL")
      )
      (libsource (lib "API") (part "RS/ERJ6ENF"))
    )
    (comp (ref "R11")
      (value "10.0k")
      (footprint "R0805")
      (description "RES 10.0K OHM 1/8W 1% 0805 SMD")
      (fields
        (field (name "MANUFACTURER") "Panasonic - ECG")
        (field (name "MANUFACTURER PART NUMBER") "ERJ-6ENF1002V")
      )
      (libsource (lib "API") (part "RS/ERJ6ENF"))
    )
    (comp (ref "R12")
      (value "499 1%")
      (footprint "R0805")
      (description "RES 499 OHM 1/8W 1% 0805 SMD")
      (fields
        (field (name "MANUFACTURER") "Panasonic - ECG")
        (field (name "MANUFACTURER PART NUMBER") "ERJ-6ENF4990V")
      )
      (libsource (lib "API") (part "RS/ERJ6ENF"))
    )
    (comp (ref "R13")
      (value "3.32k 1%")
      (footprint "R0805")
      (description "RES 3.32K OHM 1/8W 1% 0805 SMD")
      (fields
        (field (name "MANUFACTURER") "Panasonic - ECG")
        (field (name "MANUFACTURER PART NUMBER") "ERJ-6ENF3321V")
      )
      (libsource (lib "API") (part "RS/ERJ6ENF"))
    )
    (comp (ref "R14")
      (value "100K")
      (footprint "R0805")
      (description "RES 100K OHM 1/8W 1% 0805 SMD")
      (fields
        (field (name "MANUFACTURER") "Panasonic - ECG")
        (field (name "MANUFACTURER PART NUMBER") "RC0805JR-07100KL")
      )
      (libsource (lib "API") (part "RS/ERJ6ENF"))
    )
    (comp (ref "R15")
      (value "47.5k 1%")
      (footprint "R0805")
      (description "RES 47.5K OHM 1/8W 1% 0805 SMD")
      (fields
        (field (name "MANUFACTURER") "Panasonic - ECG")
        (field (name "MANUFACTURER PART NUMBER") "ERJ-6ENF4752V")
      )
      (libsource (lib "API") (part "RS/ERJ6ENF"))
    )
    (comp (ref "R16")
      (value "20.0k")
      (footprint "R0805")
      (description "RES 20.0K OHM 1/8W 1% 0805 SMD")
      (fields
        (field (name "MANUFACTURER") "Panasonic - ECG")
        (field (name "MANUFACTURER PART NUMBER") "ERJ-6ENF2002V")
      )
      (libsource (lib "API") (part "RS/ERJ6ENF"))
    )
    (comp (ref "R17")
      (value "1.0k 1%")
      (footprint "R0805")
      (description "RES 1.00K OHM 1/8W 1% 0805 SMD")
      (fields
        (field (name "MANUFACTURER") "Yageo")
        (field (name "MANUFACTURER PART NUMBER") "RC0805FR-071KL")
      )
      (libsource (lib "API") (part "RS/ERJ6ENF"))
    )
    (comp (ref "R18")
      (value "1.65K 1%")
      (footprint "R0805")
      (description "RES 1.65K OHM 1/8W 1% 0805 SMD")
      (fields
        (field (name "MANUFACTURER PART NUMBER") "ERJ-6ENF1651V")
        (field (name "MANUFACTURER") "Panasonic - ECG")
      )
      (libsource (lib "API") (part "RS/ERJ6ENF"))
    )
    (comp (ref "R19")
      (value "100K")
      (footprint "R0805")
      (description "RES 100K OHM 1/8W 1% 0805 SMD")
      (fields
        (field (name "MANUFACTURER") "Panasonic - ECG")
        (field (name "MANUFACTURER PART NUMBER") "RC0805JR-07100KL")
      )
      (libsource (lib "API") (part "RS/ERJ6ENF"))
    )
    (comp (ref "R20")
      (value "10.0k")
      (footprint "R0805")
      (description "RES 10.0K OHM 1/8W 1% 0805 SMD")
      (fields
        (field (name "MANUFACTURER") "Panasonic - ECG")
        (field (name "MANUFACTURER PART NUMBER") "ERJ-6ENF1002V")
      )
      (libsource (lib "API") (part "RS/ERJ6ENF"))
    )
    (comp (ref "R21")
      (value "100K")
      (footprint "R0805")
      (description "RES 100K OHM 1/8W 1% 0805 SMD")
      (fields
        (field (name "MANUFACTURER") "Panasonic - ECG")
        (field (name "MANUFACTURER PART NUMBER") "RC0805JR-07100KL")
      )
      (libsource (lib "API") (part "RS/ERJ6ENF"))
    )
    (comp (ref "R22")
      (value "0")
      (footprint "R0805")
      (description "RES 0.0 OHM 1/8W 5% 0805 SMD")
      (fields
        (field (name "MANUFACTURER") "Panasonic - ECG")
        (field (name "MANUFACTURER PART NUMBER") "ERJ-6GEY0R00V")
      )
      (libsource (lib "API") (part "RS/ERJ6GEYJ"))
    )
    (comp (ref "R23")
      (value "100K")
      (footprint "R0805")
      (description "RES 100K OHM 1/8W 1% 0805 SMD")
      (fields
        (field (name "MANUFACTURER") "Panasonic - ECG")
        (field (name "MANUFACTURER PART NUMBER") "RC0805JR-07100KL")
      )
      (libsource (lib "API") (part "RS/ERJ6ENF"))
    )
    (comp (ref "R24")
      (value "7.50k 1%")
      (footprint "R0805")
      (description "RES 7.50K OHM 1/8W 1% 0805 SMD")
      (fields
        (field (name "MANUFACTURER") "Panasonic - ECG")
        (field (name "MANUFACTURER PART NUMBER") "ERJ-6ENF7501V")
      )
      (libsource (lib "API") (part "RS/ERJ6ENF"))
    )
    (comp (ref "R25")
      (value "2.49k 1%")
      (description "RES 2.49K OHM 1/8W 1% 0805 SMD")
      (fields
        (field (name "MANUFACTURER") "Panasonic - ECG")
        (field (name "MANUFACTURER PART NUMBER") "ERJ-6ENF2491V")
      )
      (libsource (lib "API") (part "RS/ERJ6ENF"))
    )
    (comp (ref "R26")
      (value "100K")
      (footprint "R0805")
      (description "RES 100K OHM 1/8W 1% 0805 SMD")
      (fields
        (field (name "MANUFACTURER") "Panasonic - ECG")
        (field (name "MANUFACTURER PART NUMBER") "RC0805JR-07100KL")
      )
      (libsource (lib "API") (part "RS/ERJ6ENF"))
    )
    (comp (ref "R27")
      (value "100K")
      (footprint "R0805")
      (description "RES 100K OHM 1/8W 1% 0805 SMD")
      (fields
        (field (name "MANUFACTURER") "Panasonic - ECG")
        (field (name "MANUFACTURER PART NUMBER") "RC0805JR-07100KL")
      )
      (libsource (lib "API") (part "RS/ERJ6ENF"))
    )
    (comp (ref "R28")
      (value "1.0k 1%")
      (footprint "R0805")
      (description "RES 1.00K OHM 1/8W 1% 0805 SMD")
      (fields
        (field (name "MANUFACTURER") "Yageo")
        (field (name "MANUFACTURER PART NUMBER") "RC0805FR-071KL")
      )
      (libsource (lib "API") (part "RS/ERJ6ENF"))
    )
    (comp (ref "R29")
      (value "0")
      (footprint "R0805")
      (description "RES 0.0 OHM 1/8W 5% 0805 SMD")
      (fields
        (field (name "MANUFACTURER") "Panasonic - ECG")
        (field (name "MANUFACTURER PART NUMBER") "ERJ-6GEY0R00V")
      )
      (libsource (lib "API") (part "RS/ERJ6GEYJ"))
    )
    (comp (ref "R30")
      (value "100K")
      (footprint "R0805")
      (description "RES 100K OHM 1/8W 1% 0805 SMD")
      (fields
        (field (name "MANUFACTURER") "Panasonic - ECG")
        (field (name "MANUFACTURER PART NUMBER") "RC0805JR-07100KL")
      )
      (libsource (lib "API") (part "RS/ERJ6ENF"))
    )
    (comp (ref "R40")
      (value "1.0k 1%")
      (footprint "R0805")
      (description "RES 1.00K OHM 1/8W 1% 0805 SMD")
      (fields
        (field (name "MANUFACTURER") "Yageo")
        (field (name "MANUFACTURER PART NUMBER") "RC0805FR-071KL")
      )
      (libsource (lib "API") (part "RS/ERJ6ENF"))
    )
    (comp (ref "R46")
      (value "15.0 OHM 1%")
      (footprint "R1206")
      (description "RES 15.0 OHM 1/4W 1% 1206 SMD")
      (fields
        (field (name "MANUFACTURER") "Panasonic - ECG")
        (field (name "MANUFACTURER PART NUMBER") "ERJ-8ENF15R0V")
      )
      (libsource (lib "API") (part "RS/ERJ8ENF"))
    )
    (comp (ref "R47")
      (value "15.0 OHM 1%")
      (footprint "R1206")
      (description "RES 15.0 OHM 1/4W 1% 1206 SMD")
      (fields
        (field (name "MANUFACTURER") "Panasonic - ECG")
        (field (name "MANUFACTURER PART NUMBER") "ERJ-8ENF15R0V")
      )
      (libsource (lib "API") (part "RS/ERJ8ENF"))
    )
    (comp (ref "R48")
      (value "15.0 OHM 1%")
      (footprint "R1206")
      (description "RES 15.0 OHM 1/4W 1% 1206 SMD")
      (fields
        (field (name "MANUFACTURER") "Panasonic - ECG")
        (field (name "MANUFACTURER PART NUMBER") "ERJ-8ENF15R0V")
      )
      (libsource (lib "API") (part "RS/ERJ8ENF"))
    )
    (comp (ref "R49")
      (value "15.0 OHM 1%")
      (footprint "R1206")
      (description "RES 15.0 OHM 1/4W 1% 1206 SMD")
      (fields
        (field (name "MANUFACTURER") "Panasonic - ECG")
        (field (name "MANUFACTURER PART NUMBER") "ERJ-8ENF15R0V")
      )
      (libsource (lib "API") (part "RS/ERJ8ENF"))
    )
    (comp (ref "R50")
      (value "15.0 OHM 1%")
      (footprint "R1206")
      (description "RES 15.0 OHM 1/4W 1% 1206 SMD")
      (fields
        (field (name "MANUFACTURER") "Panasonic - ECG")
        (field (name "MANUFACTURER PART NUMBER") "ERJ-8ENF15R0V")
      )
      (libsource (lib "API") (part "RS/ERJ8ENF"))
    )
    (comp (ref "R51")
      (value "15.0 OHM 1%")
      (footprint "R1206")
      (description "RES 15.0 OHM 1/4W 1% 1206 SMD")
      (fields
        (field (name "MANUFACTURER") "Panasonic - ECG")
        (field (name "MANUFACTURER PART NUMBER") "ERJ-8ENF15R0V")
      )
      (libsource (lib "API") (part "RS/ERJ8ENF"))
    )
    (comp (ref "R52")
      (value "15.0 OHM 1%")
      (footprint "R1206")
      (description "RES 15.0 OHM 1/4W 1% 1206 SMD")
      (fields
        (field (name "MANUFACTURER") "Panasonic - ECG")
        (field (name "MANUFACTURER PART NUMBER") "ERJ-8ENF15R0V")
      )
      (libsource (lib "API") (part "RS/ERJ8ENF"))
    )
    (comp (ref "R53")
      (value "15.0 OHM 1%")
      (footprint "R1206")
      (description "RES 15.0 OHM 1/4W 1% 1206 SMD")
      (fields
        (field (name "MANUFACTURER") "Panasonic - ECG")
        (field (name "MANUFACTURER PART NUMBER") "ERJ-8ENF15R0V")
      )
      (libsource (lib "API") (part "RS/ERJ8ENF"))
    )
    (comp (ref "R54")
      (value "15.0 OHM 1%")
      (footprint "R1206")
      (description "RES 15.0 OHM 1/4W 1% 1206 SMD")
      (fields
        (field (name "MANUFACTURER") "Panasonic - ECG")
        (field (name "MANUFACTURER PART NUMBER") "ERJ-8ENF15R0V")
      )
      (libsource (lib "API") (part "RS/ERJ8ENF"))
    )
    (comp (ref "R55")
      (value "15.0 OHM 1%")
      (footprint "R1206")
      (description "RES 15.0 OHM 1/4W 1% 1206 SMD")
      (fields
        (field (name "MANUFACTURER") "Panasonic - ECG")
        (field (name "MANUFACTURER PART NUMBER") "ERJ-8ENF15R0V")
      )
      (libsource (lib "API") (part "RS/ERJ8ENF"))
    )
    (comp (ref "R56")
      (value "15.0 OHM 1%")
      (footprint "R1206")
      (description "RES 15.0 OHM 1/4W 1% 1206 SMD")
      (fields
        (field (name "MANUFACTURER") "Panasonic - ECG")
        (field (name "MANUFACTURER PART NUMBER") "ERJ-8ENF15R0V")
      )
      (libsource (lib "API") (part "RS/ERJ8ENF"))
    )
    (comp (ref "R57")
      (value "15.0 OHM 1%")
      (footprint "R1206")
      (description "RES 15.0 OHM 1/4W 1% 1206 SMD")
      (fields
        (field (name "MANUFACTURER") "Panasonic - ECG")
        (field (name "MANUFACTURER PART NUMBER") "ERJ-8ENF15R0V")
      )
      (libsource (lib "API") (part "RS/ERJ8ENF"))
    )
    (comp (ref "R58")
      (value "32.4 OHM 1%")
      (footprint "R1206")
      (description "RES 32.4 OHM 1/4W 1% 1206 SMD")
      (fields
        (field (name "MANUFACTURER") "Panasonic - ECG")
        (field (name "MANUFACTURER PART NUMBER") "ERJ-8ENF32R4V")
      )
      (libsource (lib "API") (part "RS/ERJ8ENF"))
    )
    (comp (ref "R59")
      (value "32.4 OHM 1%")
      (footprint "R1206")
      (description "RES 32.4 OHM 1/4W 1% 1206 SMD")
      (fields
        (field (name "MANUFACTURER") "Panasonic - ECG")
        (field (name "MANUFACTURER PART NUMBER") "ERJ-8ENF32R4V")
      )
      (libsource (lib "API") (part "RS/ERJ8ENF"))
    )
    (comp (ref "R60")
      (value "32.4 OHM 1%")
      (footprint "R1206")
      (description "RES 32.4 OHM 1/4W 1% 1206 SMD")
      (fields
        (field (name "MANUFACTURER") "Panasonic - ECG")
        (field (name "MANUFACTURER PART NUMBER") "ERJ-8ENF32R4V")
      )
      (libsource (lib "API") (part "RS/ERJ8ENF"))
    )
    (comp (ref "R61")
      (value "32.4 OHM 1%")
      (footprint "R1206")
      (description "RES 32.4 OHM 1/4W 1% 1206 SMD")
      (fields
        (field (name "MANUFACTURER") "Panasonic - ECG")
        (field (name "MANUFACTURER PART NUMBER") "ERJ-8ENF32R4V")
      )
      (libsource (lib "API") (part "RS/ERJ8ENF"))
    )
    (comp (ref "R62")
      (value "32.4 OHM 1%")
      (footprint "R1206")
      (description "RES 32.4 OHM 1/4W 1% 1206 SMD")
      (fields
        (field (name "MANUFACTURER") "Panasonic - ECG")
        (field (name "MANUFACTURER PART NUMBER") "ERJ-8ENF32R4V")
      )
      (libsource (lib "API") (part "RS/ERJ8ENF"))
    )
    (comp (ref "R63")
      (value "32.4 OHM 1%")
      (footprint "R1206")
      (description "RES 32.4 OHM 1/4W 1% 1206 SMD")
      (fields
        (field (name "MANUFACTURER") "Panasonic - ECG")
        (field (name "MANUFACTURER PART NUMBER") "ERJ-8ENF32R4V")
      )
      (libsource (lib "API") (part "RS/ERJ8ENF"))
    )
    (comp (ref "R64")
      (value "32.4 OHM 1%")
      (footprint "R1206")
      (description "RES 32.4 OHM 1/4W 1% 1206 SMD")
      (fields
        (field (name "MANUFACTURER") "Panasonic - ECG")
        (field (name "MANUFACTURER PART NUMBER") "ERJ-8ENF32R4V")
      )
      (libsource (lib "API") (part "RS/ERJ8ENF"))
    )
    (comp (ref "R65")
      (value "32.4 OHM 1%")
      (footprint "R1206")
      (description "RES 32.4 OHM 1/4W 1% 1206 SMD")
      (fields
        (field (name "MANUFACTURER") "Panasonic - ECG")
        (field (name "MANUFACTURER PART NUMBER") "ERJ-8ENF32R4V")
      )
      (libsource (lib "API") (part "RS/ERJ8ENF"))
    )
    (comp (ref "R66")
      (value "32.4 OHM 1%")
      (footprint "R1206")
      (description "RES 32.4 OHM 1/4W 1% 1206 SMD")
      (fields
        (field (name "MANUFACTURER") "Panasonic - ECG")
        (field (name "MANUFACTURER PART NUMBER") "ERJ-8ENF32R4V")
      )
      (libsource (lib "API") (part "RS/ERJ8ENF"))
    )
    (comp (ref "R67")
      (value "32.4 OHM 1%")
      (footprint "R1206")
      (description "RES 32.4 OHM 1/4W 1% 1206 SMD")
      (fields
        (field (name "MANUFACTURER") "Panasonic - ECG")
        (field (name "MANUFACTURER PART NUMBER") "ERJ-8ENF32R4V")
      )
      (libsource (lib "API") (part "RS/ERJ8ENF"))
    )
    (comp (ref "R68")
      (value "32.4 OHM 1%")
      (footprint "R1206")
      (description "RES 32.4 OHM 1/4W 1% 1206 SMD")
      (fields
        (field (name "MANUFACTURER") "Panasonic - ECG")
        (field (name "MANUFACTURER PART NUMBER") "ERJ-8ENF32R4V")
      )
      (libsource (lib "API") (part "RS/ERJ8ENF"))
    )
    (comp (ref "R69")
      (value "32.4 OHM 1%")
      (footprint "R1206")
      (description "RES 32.4 OHM 1/4W 1% 1206 SMD")
      (fields
        (field (name "MANUFACTURER") "Panasonic - ECG")
        (field (name "MANUFACTURER PART NUMBER") "ERJ-8ENF32R4V")
      )
      (libsource (lib "API") (part "RS/ERJ8ENF"))
    )
    (comp (ref "R88")
      (value "15.0 OHM 1%")
      (footprint "R1206")
      (description "RES 15.0 OHM 1/4W 1% 1206 SMD")
      (fields
        (field (name "MANUFACTURER") "Panasonic - ECG")
        (field (name "MANUFACTURER PART NUMBER") "ERJ-8ENF15R0V")
      )
      (libsource (lib "API") (part "RS/ERJ8ENF"))
    )
    (comp (ref "R89")
      (value "15.0 OHM 1%")
      (footprint "R1206")
      (description "RES 15.0 OHM 1/4W 1% 1206 SMD")
      (fields
        (field (name "MANUFACTURER") "Panasonic - ECG")
        (field (name "MANUFACTURER PART NUMBER") "ERJ-8ENF15R0V")
      )
      (libsource (lib "API") (part "RS/ERJ8ENF"))
    )
    (comp (ref "R90")
      (value "15.0 OHM 1%")
      (footprint "R1206")
      (description "RES 15.0 OHM 1/4W 1% 1206 SMD")
      (fields
        (field (name "MANUFACTURER") "Panasonic - ECG")
        (field (name "MANUFACTURER PART NUMBER") "ERJ-8ENF15R0V")
      )
      (libsource (lib "API") (part "RS/ERJ8ENF"))
    )
    (comp (ref "R91")
      (value "15.0 OHM 1%")
      (footprint "R1206")
      (description "RES 15.0 OHM 1/4W 1% 1206 SMD")
      (fields
        (field (name "MANUFACTURER") "Panasonic - ECG")
        (field (name "MANUFACTURER PART NUMBER") "ERJ-8ENF15R0V")
      )
      (libsource (lib "API") (part "RS/ERJ8ENF"))
    )
    (comp (ref "R92")
      (value "15.0 OHM 1%")
      (footprint "R1206")
      (description "RES 15.0 OHM 1/4W 1% 1206 SMD")
      (fields
        (field (name "MANUFACTURER") "Panasonic - ECG")
        (field (name "MANUFACTURER PART NUMBER") "ERJ-8ENF15R0V")
      )
      (libsource (lib "API") (part "RS/ERJ8ENF"))
    )
    (comp (ref "R93")
      (value "15.0 OHM 1%")
      (footprint "R1206")
      (description "RES 15.0 OHM 1/4W 1% 1206 SMD")
      (fields
        (field (name "MANUFACTURER") "Panasonic - ECG")
        (field (name "MANUFACTURER PART NUMBER") "ERJ-8ENF15R0V")
      )
      (libsource (lib "API") (part "RS/ERJ8ENF"))
    )
    (comp (ref "R94")
      (value "15.0 OHM 1%")
      (footprint "R1206")
      (description "RES 15.0 OHM 1/4W 1% 1206 SMD")
      (fields
        (field (name "MANUFACTURER") "Panasonic - ECG")
        (field (name "MANUFACTURER PART NUMBER") "ERJ-8ENF15R0V")
      )
      (libsource (lib "API") (part "RS/ERJ8ENF"))
    )
    (comp (ref "R95")
      (value "15.0 OHM 1%")
      (footprint "R1206")
      (description "RES 15.0 OHM 1/4W 1% 1206 SMD")
      (fields
        (field (name "MANUFACTURER") "Panasonic - ECG")
        (field (name "MANUFACTURER PART NUMBER") "ERJ-8ENF15R0V")
      )
      (libsource (lib "API") (part "RS/ERJ8ENF"))
    )
    (comp (ref "R96")
      (value "15.0 OHM 1%")
      (footprint "R1206")
      (description "RES 15.0 OHM 1/4W 1% 1206 SMD")
      (fields
        (field (name "MANUFACTURER") "Panasonic - ECG")
        (field (name "MANUFACTURER PART NUMBER") "ERJ-8ENF15R0V")
      )
      (libsource (lib "API") (part "RS/ERJ8ENF"))
    )
    (comp (ref "R97")
      (value "15.0 OHM 1%")
      (footprint "R1206")
      (description "RES 15.0 OHM 1/4W 1% 1206 SMD")
      (fields
        (field (name "MANUFACTURER") "Panasonic - ECG")
        (field (name "MANUFACTURER PART NUMBER") "ERJ-8ENF15R0V")
      )
      (libsource (lib "API") (part "RS/ERJ8ENF"))
    )
    (comp (ref "R98")
      (value "15.0 OHM 1%")
      (footprint "R1206")
      (description "RES 15.0 OHM 1/4W 1% 1206 SMD")
      (fields
        (field (name "MANUFACTURER") "Panasonic - ECG")
        (field (name "MANUFACTURER PART NUMBER") "ERJ-8ENF15R0V")
      )
      (libsource (lib "API") (part "RS/ERJ8ENF"))
    )
    (comp (ref "R99")
      (value "15.0 OHM 1%")
      (footprint "R1206")
      (description "RES 15.0 OHM 1/4W 1% 1206 SMD")
      (fields
        (field (name "MANUFACTURER") "Panasonic - ECG")
        (field (name "MANUFACTURER PART NUMBER") "ERJ-8ENF15R0V")
      )
      (libsource (lib "API") (part "RS/ERJ8ENF"))
    )
    (comp (ref "R100")
      (value "32.4 OHM 1%")
      (footprint "R1206")
      (description "RES 32.4 OHM 1/4W 1% 1206 SMD")
      (fields
        (field (name "MANUFACTURER") "Panasonic - ECG")
        (field (name "MANUFACTURER PART NUMBER") "ERJ-8ENF32R4V")
      )
      (libsource (lib "API") (part "RS/ERJ8ENF"))
    )
    (comp (ref "R101")
      (value "32.4 OHM 1%")
      (footprint "R1206")
      (description "RES 32.4 OHM 1/4W 1% 1206 SMD")
      (fields
        (field (name "MANUFACTURER") "Panasonic - ECG")
        (field (name "MANUFACTURER PART NUMBER") "ERJ-8ENF32R4V")
      )
      (libsource (lib "API") (part "RS/ERJ8ENF"))
    )
    (comp (ref "R102")
      (value "32.4 OHM 1%")
      (footprint "R1206")
      (description "RES 32.4 OHM 1/4W 1% 1206 SMD")
      (fields
        (field (name "MANUFACTURER") "Panasonic - ECG")
        (field (name "MANUFACTURER PART NUMBER") "ERJ-8ENF32R4V")
      )
      (libsource (lib "API") (part "RS/ERJ8ENF"))
    )
    (comp (ref "R103")
      (value "32.4 OHM 1%")
      (footprint "R1206")
      (description "RES 32.4 OHM 1/4W 1% 1206 SMD")
      (fields
        (field (name "MANUFACTURER") "Panasonic - ECG")
        (field (name "MANUFACTURER PART NUMBER") "ERJ-8ENF32R4V")
      )
      (libsource (lib "API") (part "RS/ERJ8ENF"))
    )
    (comp (ref "R104")
      (value "32.4 OHM 1%")
      (footprint "R1206")
      (description "RES 32.4 OHM 1/4W 1% 1206 SMD")
      (fields
        (field (name "MANUFACTURER") "Panasonic - ECG")
        (field (name "MANUFACTURER PART NUMBER") "ERJ-8ENF32R4V")
      )
      (libsource (lib "API") (part "RS/ERJ8ENF"))
    )
    (comp (ref "R105")
      (value "32.4 OHM 1%")
      (footprint "R1206")
      (description "RES 32.4 OHM 1/4W 1% 1206 SMD")
      (fields
        (field (name "MANUFACTURER") "Panasonic - ECG")
        (field (name "MANUFACTURER PART NUMBER") "ERJ-8ENF32R4V")
      )
      (libsource (lib "API") (part "RS/ERJ8ENF"))
    )
    (comp (ref "R106")
      (value "32.4 OHM 1%")
      (footprint "R1206")
      (description "RES 32.4 OHM 1/4W 1% 1206 SMD")
      (fields
        (field (name "MANUFACTURER") "Panasonic - ECG")
        (field (name "MANUFACTURER PART NUMBER") "ERJ-8ENF32R4V")
      )
      (libsource (lib "API") (part "RS/ERJ8ENF"))
    )
    (comp (ref "R107")
      (value "32.4 OHM 1%")
      (footprint "R1206")
      (description "RES 32.4 OHM 1/4W 1% 1206 SMD")
      (fields
        (field (name "MANUFACTURER") "Panasonic - ECG")
        (field (name "MANUFACTURER PART NUMBER") "ERJ-8ENF32R4V")
      )
      (libsource (lib "API") (part "RS/ERJ8ENF"))
    )
    (comp (ref "R108")
      (value "32.4 OHM 1%")
      (footprint "R1206")
      (description "RES 32.4 OHM 1/4W 1% 1206 SMD")
      (fields
        (field (name "MANUFACTURER") "Panasonic - ECG")
        (field (name "MANUFACTURER PART NUMBER") "ERJ-8ENF32R4V")
      )
      (libsource (lib "API") (part "RS/ERJ8ENF"))
    )
    (comp (ref "R109")
      (value "32.4 OHM 1%")
      (footprint "R1206")
      (description "RES 32.4 OHM 1/4W 1% 1206 SMD")
      (fields
        (field (name "MANUFACTURER") "Panasonic - ECG")
        (field (name "MANUFACTURER PART NUMBER") "ERJ-8ENF32R4V")
      )
      (libsource (lib "API") (part "RS/ERJ8ENF"))
    )
    (comp (ref "R110")
      (value "32.4 OHM 1%")
      (footprint "R1206")
      (description "RES 32.4 OHM 1/4W 1% 1206 SMD")
      (fields
        (field (name "MANUFACTURER") "Panasonic - ECG")
        (field (name "MANUFACTURER PART NUMBER") "ERJ-8ENF32R4V")
      )
      (libsource (lib "API") (part "RS/ERJ8ENF"))
    )
    (comp (ref "R111")
      (value "32.4 OHM 1%")
      (footprint "R1206")
      (description "RES 32.4 OHM 1/4W 1% 1206 SMD")
      (fields
        (field (name "MANUFACTURER") "Panasonic - ECG")
        (field (name "MANUFACTURER PART NUMBER") "ERJ-8ENF32R4V")
      )
      (libsource (lib "API") (part "RS/ERJ8ENF"))
    )
    (comp (ref "R112")
      (value "10.0k")
      (footprint "R0805")
      (description "RES 10.0K OHM 1/8W 1% 0805 SMD")
      (fields
        (field (name "MANUFACTURER") "Panasonic - ECG")
        (field (name "MANUFACTURER PART NUMBER") "ERJ-6ENF1002V")
      )
      (libsource (lib "API") (part "RS/ERJ6ENF"))
    )
    (comp (ref "R128")
      (value "3.16K")
      (footprint "R0805")
      (description "RES 3.16K OHM 1/8W 1% 0805 SMD")
      (fields
        (field (name "MANUFACTURER") "Panasonic - ECG")
        (field (name "MANUFACTURER PART NUMBER") "ERJ-6ENF3161V")
      )
      (libsource (lib "API") (part "RS/ERJ6ENF"))
    )
    (comp (ref "R129")
      (value "20.0k")
      (footprint "R0805")
      (description "RES 20.0K OHM 1/8W 1% 0805 SMD")
      (fields
        (field (name "MANUFACTURER") "Panasonic - ECG")
        (field (name "MANUFACTURER PART NUMBER") "ERJ-6ENF2002V")
      )
      (libsource (lib "API") (part "RS/ERJ6ENF"))
    )
    (comp (ref "R130")
      (value "10.0k")
      (footprint "R0805")
      (description "RES 10.0K OHM 1/8W 1% 0805 SMD")
      (fields
        (field (name "MANUFACTURER") "Panasonic - ECG")
        (field (name "MANUFACTURER PART NUMBER") "ERJ-6ENF1002V")
      )
      (libsource (lib "API") (part "RS/ERJ6ENF"))
    )
    (comp (ref "U1")
      (value "M25P64-VMF6G")
      (footprint "so16w")
      (description "64 MBit Serial SPI NOR FLASH")
      (fields
        (field (name "MANUFACTURER") "STMicroelectronics / Numonyx")
        (field (name "MANUFACTURER PART NUMBER") "M25P64-VMF6P")
      )
      (libsource (lib "API") (part "IS/M25P64VMF6GZ"))
    )
    (comp (ref "U2")
      (value "dsPIC30F5013-20I/PT")
      (footprint "TQFP-80")
      (description "IC DSPIC MCU/DSP 144K 80TQFP")
      (fields
        (field (name "MANUFACTURER") "Microchip Technology")
        (field (name "MANUFACTURER PART NUMBER") "DSPIC30F6014A-30I/PT")
      )
      (libsource (lib "API") (part "IS/DSPIC30F501320IPTZ_1"))
    )
    (comp (ref "U3")
      (value "SN65HVD230DR")
      (footprint "SOIC 8")
      (description "IC 3.3V CAN TXRX W/STNDBY 8-SOIC")
      (fields (field (name "MANUFACTURER") "Texas Instruments"))
      (libsource (lib "API") (part "IS/SN65HVD230DRT"))
    )
    (comp (ref "U4")
      (value "M25P64-VMF6G")
      (footprint "so16w")
      (description "64 MBit Serial SPI NOR FLASH")
      (fields
        (field (name "MANUFACTURER") "STMicroelectronics / Numonyx")
        (field (name "MANUFACTURER PART NUMBER") "M25P64-VMF6P")
      )
      (libsource (lib "API") (part "IS/M25P64VMF6GZ"))
    )
    (comp (ref "U5")
      (value "CS4344-CZZ")
      (footprint "TSSOP\\10")
      (description "IC DAC 24BIT 192KHZ 10-TSSOP")
      (fields (field (name "MANUFACTURER") "Cirrus Logic Inc"))
      (libsource (lib "API") (part "IS/CS4344CZZZ"))
    )
    (comp (ref "U6")
      (value "LM2676S-ADJ/NOPB")
      (footprint "TO263\\7")
      (description "NATIONAL SEMICONDUCTOR - LM2676S-ADJ/NOPB - IC, STEP-DOWN REGULATOR, TO-263-7")
      (fields (field (name "MANUFACTURER") "NATIONAL SEMICONDUCTOR"))
      (libsource (lib "ELC0103 - Master & ELC0104 - Slave") (part "IS/LM2676SADJN"))
    )
    (comp (ref "U7")
      (value "LP2950CDT-3.3")
      (footprint "D-PAK / TO-252AA")
      (description "IC REG VOLT MICROPWR 3.3V TO-252")
      (fields
        (field (name "MANUFACTURER") "National Semiconductor")
        (field (name "MANUFACTURER PART NUMBER") "LP2950CDT-3.3/NOPB")
      )
      (libsource (lib "API") (part "IS/LP2950CDT33N"))
    )
    (comp (ref "U8")
      (value "M25P64-VMF6G")
      (footprint "so16w")
      (description "64 MBit Serial SPI NOR FLASH")
      (fields
        (field (name "MANUFACTURER") "STMicroelectronics / Numonyx")
        (field (name "MANUFACTURER PART NUMBER") "M25P64-VMF6P")
      )
      (libsource (lib "API") (part "IS/M25P64VMF6GZ"))
    )
    (comp (ref "U9")
      (value "M25P64-VMF6G")
      (footprint "so16w")
      (description "64 MBit Serial SPI NOR FLASH")
      (fields
        (field (name "MANUFACTURER") "STMicroelectronics / Numonyx")
        (field (name "MANUFACTURER PART NUMBER") "M25P64-VMF6P")
      )
      (libsource (lib "API") (part "IS/M25P64VMF6GZ"))
    )
    (comp (ref "U10")
      (value "LM4861M")
      (footprint "M08A")
      (description "IC AMP AUDIO PWR W/SHUTDN 8-SOIC")
      (fields (field (name "MANUFACTURER") "National Semiconductor"))
      (libsource (lib "NSC Audio Power Amplifier") (part "LM4861M"))
    )
    (comp (ref "U11")
      (value "LM2676S-ADJ/NOPB")
      (footprint "TO263\\7")
      (description "NATIONAL SEMICONDUCTOR - LM2676S-ADJ/NOPB - IC, STEP-DOWN REGULATOR, TO-263-7")
      (fields (field (name "MANUFACTURER") "NATIONAL SEMICONDUCTOR"))
      (libsource (lib "ELC0103 - Master & ELC0104 - Slave") (part "IS/LM2676SADJN"))
    )
    (comp (ref "U12")
      (value "MOCD207M")
      (footprint "SOIC 8")
      (description "OPTOCOUPLER TRANS-OUT 2CH 8-SOIC")
      (fields (field (name "MANUFACTURER") "Fairchild Optoelectronics Group"))
      (libsource (lib "API") (part "I#S/MOCD207MZ"))
    )
    (comp (ref "U13")
      (value "SN74AHC1G125DBVR")
      (footprint "API:SOT23-5")
      (description "TI Tri State Buffer Single Gate")
      (fields (field (name "MANUFACTURER") "Texas Instruments"))
      (libsource (lib "API") (part "I#S/SN74AHC1G125DBVT"))
    )
    (comp (ref "U14")
      (value "IC USB-TO-UART BRIDGE 28MLP")
      (footprint "QFN-28")
      (fields
        (field (name "MANUFACTURER") "Silicon Laboratories Inc")
        (field (name "MANUFACTURER PART NUMBER") "CP2102-GM")
      )
      (libsource (lib "Playworld") (part "CP2102"))
    )
    (comp (ref "Y1")
      (value "8.192MHz")
      (footprint "XTSL\\CSM-7")
      (description "CRYSTAL 8.192MHZ 18PF FUND SMD")
      (fields
        (field (name "MANUFACTURER") "Abracon Corporation")
        (field (name "MANUFACTURER PART NUMBER") "ABLS-8.192MHZ-B2-T")
      )
      (libsource (lib "API") (part "ZS/ECS1228205PTRZ"))
    )
  )
  (nets
    (net (code "1") (name "/5V") (class "Default")
      (node (ref "C18") (pin "1") (pinfunction "1_1") (pintype "passive"))
      (node (ref "C22") (pin "1") (pinfunction "1_1") (pintype "passive"))
      (node (ref "C32") (pin "1") (pinfunction "1_1") (pintype "passive"))
      (node (ref "DS11") (pin "2") (pinfunction "A_2") (pintype "passive"))
      (node (ref "DS12") (pin "2") (pinfunction "A_2") (pintype "passive"))
      (node (ref "DS15") (pin "2") (pinfunction "A_2") (pintype "passive"))
      (node (ref "DS16") (pin "2") (pinfunction "A_2") (pintype "passive"))
      (node (ref "DS19") (pin "2") (pinfunction "A_2") (pintype "passive"))
      (node (ref "DS20") (pin "2") (pinfunction "A_2") (pintype "passive"))
      (node (ref "DS23") (pin "2") (pinfunction "A_2") (pintype "passive"))
      (node (ref "DS24") (pin "2") (pinfunction "A_2") (pintype "passive"))
      (node (ref "DS27") (pin "2") (pinfunction "A_2") (pintype "passive"))
      (node (ref "DS28") (pin "2") (pinfunction "A_2") (pintype "passive"))
      (node (ref "DS3") (pin "2") (pinfunction "A_2") (pintype "passive"))
      (node (ref "DS31") (pin "2") (pinfunction "A_2") (pintype "passive"))
      (node (ref "DS32") (pin "2") (pinfunction "A_2") (pintype "passive"))
      (node (ref "DS35") (pin "2") (pinfunction "A_2") (pintype "passive"))
      (node (ref "DS36") (pin "2") (pinfunction "A_2") (pintype "passive"))
      (node (ref "DS39") (pin "2") (pinfunction "A_2") (pintype "passive"))
      (node (ref "DS4") (pin "2") (pinfunction "A_2") (pintype "passive"))
      (node (ref "DS40") (pin "2") (pinfunction "A_2") (pintype "passive"))
      (node (ref "DS43") (pin "2") (pinfunction "A_2") (pintype "passive"))
      (node (ref "DS44") (pin "2") (pinfunction "A_2") (pintype "passive"))
      (node (ref "DS47") (pin "2") (pinfunction "A_2") (pintype "passive"))
      (node (ref "DS48") (pin "2") (pinfunction "A_2") (pintype "passive"))
      (node (ref "DS7") (pin "2") (pinfunction "A_2") (pintype "passive"))
      (node (ref "DS8") (pin "2") (pinfunction "A_2") (pintype "passive"))
      (node (ref "L1") (pin "2") (pinfunction "2_2") (pintype "passive"))
      (node (ref "R9") (pin "2") (pinfunction "2_2") (pintype "passive"))
      (node (ref "U10") (pin "6") (pinfunction "VDD_6") (pintype "power_in"))
    )
    (net (code "2") (name "/5V_DISABLE") (class "Default")
      (node (ref "R130") (pin "1") (pinfunction "1_1") (pintype "passive"))
      (node (ref "R20") (pin "1") (pinfunction "1_1") (pintype "passive"))
      (node (ref "U2") (pin "35") (pinfunction "AN14/RB14_35") (pintype "bidirectional"))
    )
    (net (code "3") (name "/AUDIO_SHUTDOWN") (class "Default")
      (node (ref "R15") (pin "1") (pinfunction "1_1") (pintype "passive"))
      (node (ref "U10") (pin "1") (pinfunction "SD_1") (pintype "input"))
      (node (ref "U13") (pin "1") (pinfunction "~{OE}_1") (pintype "input"))
      (node (ref "U2") (pin "46") (pinfunction "SDA/RG3_46") (pintype "bidirectional"))
    )
    (net (code "4") (name "/CANRX") (class "Default")
      (node (ref "U2") (pin "72") (pinfunction "C1RX/RF0_72") (pintype "bidirectional"))
      (node (ref "U3") (pin "4") (pinfunction "R_4") (pintype "output"))
    )
    (net (code "5") (name "/CANTX") (class "Default")
      (node (ref "U2") (pin "73") (pinfunction "C1TX/RF1_73") (pintype "bidirectional"))
      (node (ref "U3") (pin "1") (pinfunction "D_1") (pintype "input"))
    )
    (net (code "6") (name "/CAN_~{HS}{slash}STBY") (class "Default")
      (node (ref "U2") (pin "34") (pinfunction "AN13/RB13_34") (pintype "bidirectional"))
      (node (ref "U3") (pin "8") (pinfunction "~{HS}/STBY_8") (pintype "input"))
    )
    (net (code "7") (name "/COFS") (class "Default")
      (node (ref "U2") (pin "1") (pinfunction "COFS/RG15_1") (pintype "bidirectional"))
      (node (ref "U5") (pin "3") (pinfunction "LRCLK_3") (pintype "passive"))
    )
    (net (code "8") (name "/CSCK") (class "Default")
      (node (ref "U2") (pin "78") (pinfunction "CSCK/RG14_78") (pintype "bidirectional"))
      (node (ref "U5") (pin "2") (pinfunction "~{DEM}/SCLK_2") (pintype "passive"))
    )
    (net (code "9") (name "/CSDO") (class "Default")
      (node (ref "U2") (pin "80") (pinfunction "CSDO/RG13_80") (pintype "bidirectional"))
      (node (ref "U5") (pin "1") (pinfunction "SDIN_1") (pintype "passive"))
    )
    (net (code "10") (name "/LED0") (class "Default")
      (node (ref "R28") (pin "1") (pinfunction "1_1") (pintype "passive"))
      (node (ref "U2") (pin "58") (pinfunction "EMUC2/OC1/RD0_58") (pintype "bidirectional"))
    )
    (net (code "11") (name "/LED1") (class "Default")
      (node (ref "R40") (pin "1") (pinfunction "1_1") (pintype "passive"))
      (node (ref "U2") (pin "61") (pinfunction "EMUD2/OC2/RD1_61") (pintype "bidirectional"))
    )
    (net (code "12") (name "/MCLK") (class "Default")
      (node (ref "R29") (pin "2") (pinfunction "2_2") (pintype "passive"))
      (node (ref "R30") (pin "1") (pinfunction "1_1") (pintype "passive"))
      (node (ref "U13") (pin "4") (pinfunction "Y_4") (pintype "output"))
      (node (ref "U5") (pin "4") (pinfunction "MCLK_4") (pintype "passive"))
    )
    (net (code "13") (name "/MCLR") (class "Default")
      (node (ref "J14") (pin "1") (pinfunction "1_1") (pintype "passive"))
      (node (ref "R4") (pin "1") (pinfunction "1_1") (pintype "passive"))
      (node (ref "U2") (pin "9") (pinfunction "~{MCLR}_9") (pintype "input"))
    )
    (net (code "14") (name "/MEM_~{W}") (class "Default")
      (node (ref "R1") (pin "2") (pinfunction "2_2") (pintype "passive"))
      (node (ref "U1") (pin "9") (pinfunction "~{W}/VPP_9") (pintype "input"))
      (node (ref "U2") (pin "36") (pinfunction "AN15/OCFB/CN12/RB15_36") (pintype "bidirectional"))
      (node (ref "U4") (pin "9") (pinfunction "~{W}/VPP_9") (pintype "input"))
      (node (ref "U8") (pin "9") (pinfunction "~{W}/VPP_9") (pintype "input"))
      (node (ref "U9") (pin "9") (pinfunction "~{W}/VPP_9") (pintype "input"))
    )
    (net (code "15") (name "/OPTION0") (class "Default")
      (node (ref "JP4") (pin "1") (pinfunction "1_1") (pintype "passive"))
      (node (ref "R27") (pin "1") (pinfunction "1_1") (pintype "passive"))
      (node (ref "U2") (pin "76") (pinfunction "CN22/RA6_76") (pintype "bidirectional"))
    )
    (net (code "16") (name "/OPTION1") (class "Default")
      (node (ref "JP3") (pin "1") (pinfunction "1_1") (pintype "passive"))
      (node (ref "R26") (pin "1") (pinfunction "1_1") (pintype "passive"))
      (node (ref "U2") (pin "77") (pinfunction "CN23/RA7_77") (pintype "bidirectional"))
    )
    (net (code "17") (name "/OPTION2") (class "Default")
      (node (ref "JP2") (pin "1") (pinfunction "1_1") (pintype "passive"))
      (node (ref "R23") (pin "1") (pinfunction "1_1") (pintype "passive"))
      (node (ref "U2") (pin "23") (pinfunction "VREF-/RA9_23") (pintype "bidirectional"))
    )
    (net (code "18") (name "/OPTION3") (class "Default")
      (node (ref "JP1") (pin "1") (pinfunction "1_1") (pintype "passive"))
      (node (ref "R19") (pin "1") (pinfunction "1_1") (pintype "passive"))
      (node (ref "U2") (pin "24") (pinfunction "VREF+/RA10_24") (pintype "bidirectional"))
    )
    (net (code "19") (name "/PGC") (class "Default")
      (node (ref "J14") (pin "5") (pinfunction "5_5") (pintype "passive"))
      (node (ref "U2") (pin "19") (pinfunction "AN1/CN3/RB1_19") (pintype "bidirectional"))
    )
    (net (code "20") (name "/PGD") (class "Default")
      (node (ref "J14") (pin "4") (pinfunction "4_4") (pintype "passive"))
      (node (ref "U2") (pin "20") (pinfunction "AN0/CN2/RB0_20") (pintype "bidirectional"))
    )
    (net (code "21") (name "/PIEZO_INPUT") (class "Default")
      (node (ref "R129") (pin "1") (pinfunction "1_1") (pintype "passive"))
      (node (ref "R22") (pin "2") (pinfunction "2_2") (pintype "passive"))
      (node (ref "U12") (pin "8") (pinfunction "8_8") (pintype "passive"))
      (node (ref "U2") (pin "69") (pinfunction "OC8/CN16/RD7_69") (pintype "bidirectional"))
      (node (ref "U2") (pin "74") (pinfunction "C2TX/RG1_74") (pintype "bidirectional"))
    )
    (net (code "22") (name "/RXD2") (class "Default")
      (node (ref "U14") (pin "26") (pinfunction "TXD_26") (pintype "output"))
      (node (ref "U2") (pin "39") (pinfunction "U2RX/CN17/RF4_39") (pintype "bidirectional"))
    )
    (net (code "23") (name "/SCK") (class "Default")
      (node (ref "U1") (pin "16") (pinfunction "CLK_16") (pintype "input"))
      (node (ref "U2") (pin "45") (pinfunction "EMUC3/SCK1/INT0/RF6_45") (pintype "bidirectional"))
      (node (ref "U4") (pin "16") (pinfunction "CLK_16") (pintype "input"))
      (node (ref "U8") (pin "16") (pinfunction "CLK_16") (pintype "input"))
      (node (ref "U9") (pin "16") (pinfunction "CLK_16") (pintype "input"))
    )
    (net (code "24") (name "/SDI") (class "Default")
      (node (ref "R21") (pin "1") (pinfunction "1_1") (pintype "passive"))
      (node (ref "U1") (pin "8") (pinfunction "Q_8") (pintype "tri_state"))
      (node (ref "U2") (pin "44") (pinfunction "SDI1/RF7_44") (pintype "bidirectional"))
      (node (ref "U4") (pin "8") (pinfunction "Q_8") (pintype "tri_state"))
      (node (ref "U8") (pin "8") (pinfunction "Q_8") (pintype "tri_state"))
      (node (ref "U9") (pin "8") (pinfunction "Q_8") (pintype "tri_state"))
    )
    (net (code "25") (name "/SDO") (class "Default")
      (node (ref "U1") (pin "15") (pinfunction "D_15") (pintype "input"))
      (node (ref "U2") (pin "43") (pinfunction "EMUD3/SDO1/RF8_43") (pintype "bidirectional"))
      (node (ref "U4") (pin "15") (pinfunction "D_15") (pintype "input"))
      (node (ref "U8") (pin "15") (pinfunction "D_15") (pintype "input"))
      (node (ref "U9") (pin "15") (pinfunction "D_15") (pintype "input"))
    )
    (net (code "26") (name "/TXD2") (class "Default")
      (node (ref "U14") (pin "25") (pinfunction "RXD_25") (pintype "input"))
      (node (ref "U2") (pin "40") (pinfunction "U2TX/CN18/RF5_40") (pintype "bidirectional"))
    )
    (net (code "27") (name "/USB_RST") (class "Default")
      (node (ref "R112") (pin "1") (pinfunction "1_1") (pintype "passive"))
      (node (ref "U14") (pin "9") (pinfunction "~{RST}_9") (pintype "bidirectional"))
      (node (ref "U2") (pin "75") (pinfunction "C2RX/RG0_75") (pintype "bidirectional"))
    )
    (net (code "28") (name "/VIN_SENSE_ANALOG") (class "Default")
      (node (ref "C37") (pin "1") (pinfunction "1_1") (pintype "passive"))
      (node (ref "R24") (pin "1") (pinfunction "1_1") (pintype "passive"))
      (node (ref "R25") (pin "2") (pinfunction "2_2") (pintype "passive"))
      (node (ref "U2") (pin "18") (pinfunction "AN2/~{SS1}/LVDIN/CN4/RB2_18") (pintype "bidirectional"))
    )
    (net (code "29") (name "/V_IN") (class "Default")
      (node (ref "C10") (pin "1") (pinfunction "1_1") (pintype "passive"))
      (node (ref "C13") (pin "1") (pinfunction "1_1") (pintype "passive"))
      (node (ref "C34") (pin "1") (pinfunction "1_1") (pintype "passive"))
      (node (ref "C5") (pin "1") (pinfunction "1_1") (pintype "passive"))
      (node (ref "C7") (pin "1") (pinfunction "1_1") (pintype "passive"))
      (node (ref "D1") (pin "K") (pinfunction "K_K") (pintype "passive"))
      (node (ref "R24") (pin "2") (pinfunction "2_2") (pintype "passive"))
      (node (ref "U11") (pin "2") (pinfunction "IN_2") (pintype "power_in"))
      (node (ref "U12") (pin "1") (pinfunction "1_1") (pintype "passive"))
      (node (ref "U12") (pin "4") (pinfunction "4_4") (pintype "passive"))
      (node (ref "U6") (pin "2") (pinfunction "IN_2") (pintype "power_in"))
      (node (ref "U7") (pin "1") (pinfunction "IN_1") (pintype "power_in"))
    )
    (net (code "30") (name "/V_RED") (class "Default")
      (node (ref "C30") (pin "1") (pinfunction "1_1") (pintype "passive"))
      (node (ref "C31") (pin "1") (pinfunction "1_1") (pintype "passive"))
      (node (ref "DS1") (pin "2") (pinfunction "A_2") (pintype "passive"))
      (node (ref "DS10") (pin "2") (pinfunction "A_2") (pintype "passive"))
      (node (ref "DS13") (pin "2") (pinfunction "A_2") (pintype "passive"))
      (node (ref "DS14") (pin "2") (pinfunction "A_2") (pintype "passive"))
      (node (ref "DS17") (pin "2") (pinfunction "A_2") (pintype "passive"))
      (node (ref "DS18") (pin "2") (pinfunction "A_2") (pintype "passive"))
      (node (ref "DS2") (pin "2") (pinfunction "A_2") (pintype "passive"))
      (node (ref "DS21") (pin "2") (pinfunction "A_2") (pintype "passive"))
      (node (ref "DS22") (pin "2") (pinfunction "A_2") (pintype "passive"))
      (node (ref "DS25") (pin "2") (pinfunction "A_2") (pintype "passive"))
      (node (ref "DS26") (pin "2") (pinfunction "A_2") (pintype "passive"))
      (node (ref "DS29") (pin "2") (pinfunction "A_2") (pintype "passive"))
      (node (ref "DS30") (pin "2") (pinfunction "A_2") (pintype "passive"))
      (node (ref "DS33") (pin "2") (pinfunction "A_2") (pintype "passive"))
      (node (ref "DS34") (pin "2") (pinfunction "A_2") (pintype "passive"))
      (node (ref "DS37") (pin "2") (pinfunction "A_2") (pintype "passive"))
      (node (ref "DS38") (pin "2") (pinfunction "A_2") (pintype "passive"))
      (node (ref "DS41") (pin "2") (pinfunction "A_2") (pintype "passive"))
      (node (ref "DS42") (pin "2") (pinfunction "A_2") (pintype "passive"))
      (node (ref "DS45") (pin "2") (pinfunction "A_2") (pintype "passive"))
      (node (ref "DS46") (pin "2") (pinfunction "A_2") (pintype "passive"))
      (node (ref "DS5") (pin "2") (pinfunction "A_2") (pintype "passive"))
      (node (ref "DS6") (pin "2") (pinfunction "A_2") (pintype "passive"))
      (node (ref "DS9") (pin "2") (pinfunction "A_2") (pintype "passive"))
      (node (ref "L2") (pin "2") (pinfunction "2_2") (pintype "passive"))
      (node (ref "R18") (pin "2") (pinfunction "2_2") (pintype "passive"))
    )
    (net (code "31") (name "/~{MEM0}") (class "Default")
      (node (ref "R3") (pin "1") (pinfunction "1_1") (pintype "passive"))
      (node (ref "U1") (pin "7") (pinfunction "~{S}_7") (pintype "input"))
      (node (ref "U2") (pin "13") (pinfunction "INT1/RA12_13") (pintype "bidirectional"))
    )
    (net (code "32") (name "/~{MEM1}") (class "Default")
      (node (ref "R6") (pin "1") (pinfunction "1_1") (pintype "passive"))
      (node (ref "U2") (pin "14") (pinfunction "INT2/RA13_14") (pintype "bidirectional"))
      (node (ref "U4") (pin "7") (pinfunction "~{S}_7") (pintype "input"))
    )
    (net (code "33") (name "/~{MEM2}") (class "Default")
      (node (ref "R10") (pin "1") (pinfunction "1_1") (pintype "passive"))
      (node (ref "U2") (pin "52") (pinfunction "INT3/RA14_52") (pintype "bidirectional"))
      (node (ref "U8") (pin "7") (pinfunction "~{S}_7") (pintype "input"))
    )
    (net (code "34") (name "/~{MEM3}") (class "Default")
      (node (ref "R14") (pin "1") (pinfunction "1_1") (pintype "passive"))
      (node (ref "U2") (pin "53") (pinfunction "INT4/RA15_53") (pintype "bidirectional"))
      (node (ref "U9") (pin "7") (pinfunction "~{S}_7") (pintype "input"))
    )
    (net (code "35") (name "GND") (class "Default")
      (node (ref "C1") (pin "2") (pinfunction "2_2") (pintype "passive"))
      (node (ref "C10") (pin "2") (pinfunction "2_2") (pintype "passive"))
      (node (ref "C11") (pin "2") (pinfunction "2_2") (pintype "passive"))
      (node (ref "C13") (pin "2") (pinfunction "2_2") (pintype "passive"))
      (node (ref "C14") (pin "2") (pinfunction "2_2") (pintype "passive"))
      (node (ref "C16") (pin "2") (pinfunction "2_2") (pintype "passive"))
      (node (ref "C17") (pin "2") (pinfunction "2_2") (pintype "passive"))
      (node (ref "C18") (pin "2") (pinfunction "2_2") (pintype "passive"))
      (node (ref "C19") (pin "2") (pinfunction "2_2") (pintype "passive"))
      (node (ref "C2") (pin "2") (pinfunction "2_2") (pintype "passive"))
      (node (ref "C20") (pin "2") (pinfunction "2_2") (pintype "passive"))
      (node (ref "C21") (pin "2") (pinfunction "2_2") (pintype "passive"))
      (node (ref "C22") (pin "2") (pinfunction "2_2") (pintype "passive"))
      (node (ref "C23") (pin "2") (pinfunction "2_2") (pintype "passive"))
      (node (ref "C24") (pin "2") (pinfunction "2_2") (pintype "passive"))
      (node (ref "C28") (pin "2") (pinfunction "2_2") (pintype "passive"))
      (node (ref "C3") (pin "2") (pinfunction "2_2") (pintype "passive"))
      (node (ref "C30") (pin "2") (pinfunction "2_2") (pintype "passive"))
      (node (ref "C31") (pin "2") (pinfunction "2_2") (pintype "passive"))
      (node (ref "C32") (pin "2") (pinfunction "2_2") (pintype "passive"))
      (node (ref "C33") (pin "2") (pinfunction "2_2") (pintype "passive"))
      (node (ref "C34") (pin "2") (pinfunction "2_2") (pintype "passive"))
      (node (ref "C37") (pin "2") (pinfunction "2_2") (pintype "passive"))
      (node (ref "C4") (pin "2") (pinfunction "2_2") (pintype "passive"))
      (node (ref "C42") (pin "2") (pinfunction "2_2") (pintype "passive"))
      (node (ref "C5") (pin "2") (pinfunction "2_2") (pintype "passive"))
      (node (ref "C6") (pin "2") (pinfunction "2_2") (pintype "passive"))
      (node (ref "C7") (pin "2") (pinfunction "2_2") (pintype "passive"))
      (node (ref "C8") (pin "2") (pinfunction "2_2") (pintype "passive"))
      (node (ref "C9") (pin "2") (pinfunction "2_2") (pintype "passive"))
      (node (ref "D2") (pin "3") (pinfunction "A_3") (pintype "passive"))
      (node (ref "D3") (pin "1") (pinfunction "A_1") (pintype "passive"))
      (node (ref "D4") (pin "1") (pinfunction "A_1") (pintype "passive"))
      (node (ref "D5") (pin "1") (pinfunction "A_1") (pintype "passive"))
      (node (ref "D7") (pin "3") (pinfunction "A_3") (pintype "passive"))
      (node (ref "DS49") (pin "2") (pinfunction "K_2") (pintype "passive"))
      (node (ref "DS50") (pin "2") (pinfunction "K_2") (pintype "passive"))
      (node (ref "J1") (pin "1") (pinfunction ".125_AMP-IN_1") (pintype "passive"))
      (node (ref "J12") (pin "1") (pinfunction ".125_AMP-IN_1") (pintype "passive"))
      (node (ref "J13") (pin "4") (pinfunction "GND_4") (pintype "power_in"))
      (node (ref "J14") (pin "3") (pinfunction "3_3") (pintype "passive"))
      (node (ref "J5") (pin "1") (pinfunction ".125_AMP-IN_1") (pintype "passive"))
      (node (ref "JP1") (pin "2") (pinfunction "2_2") (pintype "passive"))
      (node (ref "JP2") (pin "2") (pinfunction "2_2") (pintype "passive"))
      (node (ref "JP3") (pin "2") (pinfunction "2_2") (pintype "passive"))
      (node (ref "JP4") (pin "2") (pinfunction "2_2") (pintype "passive"))
      (node (ref "Q1") (pin "1") (pinfunction "S_1") (pintype "passive"))
      (node (ref "Q1") (pin "2") (pinfunction "S_2") (pintype "passive"))
      (node (ref "Q1") (pin "3") (pinfunction "S_3") (pintype "passive"))
      (node (ref "Q2") (pin "1") (pinfunction "S_1") (pintype "passive"))
      (node (ref "Q2") (pin "2") (pinfunction "S_2") (pintype "passive"))
      (node (ref "Q2") (pin "3") (pinfunction "S_3") (pintype "passive"))
      (node (ref "R11") (pin "1") (pinfunction "1_1") (pintype "passive"))
      (node (ref "R17") (pin "1") (pinfunction "1_1") (pintype "passive"))
      (node (ref "R25") (pin "1") (pinfunction "1_1") (pintype "passive"))
      (node (ref "R7") (pin "1") (pinfunction "1_1") (pintype "passive"))
      (node (ref "U1") (pin "10") (pinfunction "VSS_10") (pintype "power_in"))
      (node (ref "U10") (pin "7") (pinfunction "GND_7") (pintype "power_in"))
      (node (ref "U11") (pin "4") (pinfunction "GND_4") (pintype "power_in"))
      (node (ref "U11") (pin "8") (pinfunction "GND_8") (pintype "power_in"))
      (node (ref "U12") (pin "7") (pinfunction "7_7") (pintype "passive"))
      (node (ref "U13") (pin "3") (pinfunction "GND_3") (pintype "power_in"))
      (node (ref "U14") (pin "29") (pinfunction "THERMAL_PAD_29") (pintype "passive"))
      (node (ref "U14") (pin "3") (pinfunction "GND_3") (pintype "power_in"))
      (node (ref "U2") (pin "11") (pinfunction "VSS_11") (pintype "power_in"))
      (node (ref "U2") (pin "26") (pinfunction "AVSS_26") (pintype "power_in"))
      (node (ref "U2") (pin "31") (pinfunction "VSS_31") (pintype "power_in"))
      (node (ref "U2") (pin "51") (pinfunction "VSS_51") (pintype "power_in"))
      (node (ref "U2") (pin "70") (pinfunction "VSS_70") (pintype "power_in"))
      (node (ref "U2") (pin "79") (pinfunction "CSDI/RG12_79") (pintype "bidirectional"))
      (node (ref "U3") (pin "2") (pinfunction "GND_2") (pintype "power_in"))
      (node (ref "U4") (pin "10") (pinfunction "VSS_10") (pintype "power_in"))
      (node (ref "U5") (pin "8") (pinfunction "GND_8") (pintype "passive"))
      (node (ref "U6") (pin "4") (pinfunction "GND_4") (pintype "power_in"))
      (node (ref "U6") (pin "8") (pinfunction "GND_8") (pintype "power_in"))
      (node (ref "U7") (pin "2") (pinfunction "GND_2") (pintype "power_in"))
      (node (ref "U8") (pin "10") (pinfunction "VSS_10") (pintype "power_in"))
      (node (ref "U9") (pin "10") (pinfunction "VSS_10") (pintype "power_in"))
    )
    (net (code "36") (name "Net-(C15-Pad2)") (class "Default")
      (node (ref "C15") (pin "2") (pinfunction "2_2") (pintype "passive"))
      (node (ref "R11") (pin "2") (pinfunction "2_2") (pintype "passive"))
      (node (ref "R12") (pin "1") (pinfunction "1_1") (pintype "passive"))
    )
    (net (code "37") (name "Net-(C24-Pad1)") (class "Default")
      (node (ref "C24") (pin "1") (pinfunction "1_1") (pintype "passive"))
      (node (ref "C25") (pin "1") (pinfunction "1_1") (pintype "passive"))
      (node (ref "R12") (pin "2") (pinfunction "2_2") (pintype "passive"))
    )
    (net (code "38") (name "Net-(C25-Pad2)") (class "Default")
      (node (ref "C25") (pin "2") (pinfunction "2_2") (pintype "passive"))
      (node (ref "R13") (pin "1") (pinfunction "1_1") (pintype "passive"))
    )
    (net (code "39") (name "Net-(D2-K)") (class "Default")
      (node (ref "C12") (pin "2") (pinfunction "2_2") (pintype "passive"))
      (node (ref "D2") (pin "2") (pinfunction "K_2") (pintype "passive"))
      (node (ref "L1") (pin "1") (pinfunction "1_1") (pintype "passive"))
      (node (ref "U6") (pin "1") (pinfunction "OUT_1") (pintype "power_in"))
    )
    (net (code "40") (name "Net-(D3-K)") (class "Default")
      (node (ref "D3") (pin "3") (pinfunction "K_3") (pintype "passive"))
      (node (ref "J13") (pin "1") (pinfunction "VBUS_1") (pintype "power_in"))
      (node (ref "U14") (pin "8") (pinfunction "VBUS_8") (pintype "input"))
    )
    (net (code "41") (name "Net-(D4-K)") (class "Default")
      (node (ref "D4") (pin "3") (pinfunction "K_3") (pintype "passive"))
      (node (ref "J13") (pin "2") (pinfunction "D-_2") (pintype "input"))
      (node (ref "U14") (pin "5") (pinfunction "D-_5") (pintype "bidirectional"))
    )
    (net (code "42") (name "Net-(D5-K)") (class "Default")
      (node (ref "D5") (pin "3") (pinfunction "K_3") (pintype "passive"))
      (node (ref "J13") (pin "3") (pinfunction "D+_3") (pintype "input"))
      (node (ref "U14") (pin "4") (pinfunction "D+_4") (pintype "bidirectional"))
    )
    (net (code "43") (name "Net-(D7-K)") (class "Default")
      (node (ref "C26") (pin "2") (pinfunction "2_2") (pintype "passive"))
      (node (ref "D7") (pin "2") (pinfunction "K_2") (pintype "passive"))
      (node (ref "L2") (pin "1") (pinfunction "1_1") (pintype "passive"))
      (node (ref "U11") (pin "1") (pinfunction "OUT_1") (pintype "power_in"))
    )
    (net (code "44") (name "Net-(DS1-K-Pad1)") (class "Default")
      (node (ref "DS1") (pin "1") (pinfunction "K_1") (pintype "passive"))
      (node (ref "DS1") (pin "3") (pinfunction "K_3") (pintype "passive"))
      (node (ref "DS1") (pin "4") (pinfunction "K_4") (pintype "passive"))
      (node (ref "R46") (pin "2") (pinfunction "2_2") (pintype "passive"))
    )
    (net (code "45") (name "Net-(DS2-K-Pad1)") (class "Default")
      (node (ref "DS2") (pin "1") (pinfunction "K_1") (pintype "passive"))
      (node (ref "DS2") (pin "3") (pinfunction "K_3") (pintype "passive"))
      (node (ref "DS2") (pin "4") (pinfunction "K_4") (pintype "passive"))
      (node (ref "R47") (pin "2") (pinfunction "2_2") (pintype "passive"))
    )
    (net (code "46") (name "Net-(DS3-K-Pad1)") (class "Default")
      (node (ref "DS3") (pin "1") (pinfunction "K_1") (pintype "passive"))
      (node (ref "DS3") (pin "3") (pinfunction "K_3") (pintype "passive"))
      (node (ref "DS3") (pin "4") (pinfunction "K_4") (pintype "passive"))
      (node (ref "R58") (pin "2") (pinfunction "2_2") (pintype "passive"))
    )
    (net (code "47") (name "Net-(DS4-K-Pad1)") (class "Default")
      (node (ref "DS4") (pin "1") (pinfunction "K_1") (pintype "passive"))
      (node (ref "DS4") (pin "3") (pinfunction "K_3") (pintype "passive"))
      (node (ref "DS4") (pin "4") (pinfunction "K_4") (pintype "passive"))
      (node (ref "R59") (pin "2") (pinfunction "2_2") (pintype "passive"))
    )
    (net (code "48") (name "Net-(DS5-K-Pad1)") (class "Default")
      (node (ref "DS5") (pin "1") (pinfunction "K_1") (pintype "passive"))
      (node (ref "DS5") (pin "3") (pinfunction "K_3") (pintype "passive"))
      (node (ref "DS5") (pin "4") (pinfunction "K_4") (pintype "passive"))
      (node (ref "R48") (pin "2") (pinfunction "2_2") (pintype "passive"))
    )
    (net (code "49") (name "Net-(DS6-K-Pad1)") (class "Default")
      (node (ref "DS6") (pin "1") (pinfunction "K_1") (pintype "passive"))
      (node (ref "DS6") (pin "3") (pinfunction "K_3") (pintype "passive"))
      (node (ref "DS6") (pin "4") (pinfunction "K_4") (pintype "passive"))
      (node (ref "R49") (pin "2") (pinfunction "2_2") (pintype "passive"))
    )
    (net (code "50") (name "Net-(DS7-K-Pad1)") (class "Default")
      (node (ref "DS7") (pin "1") (pinfunction "K_1") (pintype "passive"))
      (node (ref "DS7") (pin "3") (pinfunction "K_3") (pintype "passive"))
      (node (ref "DS7") (pin "4") (pinfunction "K_4") (pintype "passive"))
      (node (ref "R60") (pin "2") (pinfunction "2_2") (pintype "passive"))
    )
    (net (code "51") (name "Net-(DS8-K-Pad1)") (class "Default")
      (node (ref "DS8") (pin "1") (pinfunction "K_1") (pintype "passive"))
      (node (ref "DS8") (pin "3") (pinfunction "K_3") (pintype "passive"))
      (node (ref "DS8") (pin "4") (pinfunction "K_4") (pintype "passive"))
      (node (ref "R61") (pin "2") (pinfunction "2_2") (pintype "passive"))
    )
    (net (code "52") (name "Net-(DS9-K-Pad1)") (class "Default")
      (node (ref "DS9") (pin "1") (pinfunction "K_1") (pintype "passive"))
      (node (ref "DS9") (pin "3") (pinfunction "K_3") (pintype "passive"))
      (node (ref "DS9") (pin "4") (pinfunction "K_4") (pintype "passive"))
      (node (ref "R50") (pin "2") (pinfunction "2_2") (pintype "passive"))
    )
    (net (code "53") (name "Net-(DS10-K-Pad1)") (class "Default")
      (node (ref "DS10") (pin "1") (pinfunction "K_1") (pintype "passive"))
      (node (ref "DS10") (pin "3") (pinfunction "K_3") (pintype "passive"))
      (node (ref "DS10") (pin "4") (pinfunction "K_4") (pintype "passive"))
      (node (ref "R51") (pin "2") (pinfunction "2_2") (pintype "passive"))
    )
    (net (code "54") (name "Net-(DS11-K-Pad1)") (class "Default")
      (node (ref "DS11") (pin "1") (pinfunction "K_1") (pintype "passive"))
      (node (ref "DS11") (pin "3") (pinfunction "K_3") (pintype "passive"))
      (node (ref "DS11") (pin "4") (pinfunction "K_4") (pintype "passive"))
      (node (ref "R62") (pin "2") (pinfunction "2_2") (pintype "passive"))
    )
    (net (code "55") (name "Net-(DS12-K-Pad1)") (class "Default")
      (node (ref "DS12") (pin "1") (pinfunction "K_1") (pintype "passive"))
      (node (ref "DS12") (pin "3") (pinfunction "K_3") (pintype "passive"))
      (node (ref "DS12") (pin "4") (pinfunction "K_4") (pintype "passive"))
      (node (ref "R63") (pin "2") (pinfunction "2_2") (pintype "passive"))
    )
    (net (code "56") (name "Net-(DS13-K-Pad1)") (class "Default")
      (node (ref "DS13") (pin "1") (pinfunction "K_1") (pintype "passive"))
      (node (ref "DS13") (pin "3") (pinfunction "K_3") (pintype "passive"))
      (node (ref "DS13") (pin "4") (pinfunction "K_4") (pintype "passive"))
      (node (ref "R52") (pin "2") (pinfunction "2_2") (pintype "passive"))
    )
    (net (code "57") (name "Net-(DS14-K-Pad1)") (class "Default")
      (node (ref "DS14") (pin "1") (pinfunction "K_1") (pintype "passive"))
      (node (ref "DS14") (pin "3") (pinfunction "K_3") (pintype "passive"))
      (node (ref "DS14") (pin "4") (pinfunction "K_4") (pintype "passive"))
      (node (ref "R53") (pin "2") (pinfunction "2_2") (pintype "passive"))
    )
    (net (code "58") (name "Net-(DS15-K-Pad1)") (class "Default")
      (node (ref "DS15") (pin "1") (pinfunction "K_1") (pintype "passive"))
      (node (ref "DS15") (pin "3") (pinfunction "K_3") (pintype "passive"))
      (node (ref "DS15") (pin "4") (pinfunction "K_4") (pintype "passive"))
      (node (ref "R64") (pin "2") (pinfunction "2_2") (pintype "passive"))
    )
    (net (code "59") (name "Net-(DS16-K-Pad1)") (class "Default")
      (node (ref "DS16") (pin "1") (pinfunction "K_1") (pintype "passive"))
      (node (ref "DS16") (pin "3") (pinfunction "K_3") (pintype "passive"))
      (node (ref "DS16") (pin "4") (pinfunction "K_4") (pintype "passive"))
      (node (ref "R65") (pin "2") (pinfunction "2_2") (pintype "passive"))
    )
    (net (code "60") (name "Net-(DS17-K-Pad1)") (class "Default")
      (node (ref "DS17") (pin "1") (pinfunction "K_1") (pintype "passive"))
      (node (ref "DS17") (pin "3") (pinfunction "K_3") (pintype "passive"))
      (node (ref "DS17") (pin "4") (pinfunction "K_4") (pintype "passive"))
      (node (ref "R54") (pin "2") (pinfunction "2_2") (pintype "passive"))
    )
    (net (code "61") (name "Net-(DS18-K-Pad1)") (class "Default")
      (node (ref "DS18") (pin "1") (pinfunction "K_1") (pintype "passive"))
      (node (ref "DS18") (pin "3") (pinfunction "K_3") (pintype "passive"))
      (node (ref "DS18") (pin "4") (pinfunction "K_4") (pintype "passive"))
      (node (ref "R55") (pin "2") (pinfunction "2_2") (pintype "passive"))
    )
    (net (code "62") (name "Net-(DS19-K-Pad1)") (class "Default")
      (node (ref "DS19") (pin "1") (pinfunction "K_1") (pintype "passive"))
      (node (ref "DS19") (pin "3") (pinfunction "K_3") (pintype "passive"))
      (node (ref "DS19") (pin "4") (pinfunction "K_4") (pintype "passive"))
      (node (ref "R66") (pin "2") (pinfunction "2_2") (pintype "passive"))
    )
    (net (code "63") (name "Net-(DS20-K-Pad1)") (class "Default")
      (node (ref "DS20") (pin "1") (pinfunction "K_1") (pintype "passive"))
      (node (ref "DS20") (pin "3") (pinfunction "K_3") (pintype "passive"))
      (node (ref "DS20") (pin "4") (pinfunction "K_4") (pintype "passive"))
      (node (ref "R67") (pin "2") (pinfunction "2_2") (pintype "passive"))
    )
    (net (code "64") (name "Net-(DS21-K-Pad1)") (class "Default")
      (node (ref "DS21") (pin "1") (pinfunction "K_1") (pintype "passive"))
      (node (ref "DS21") (pin "3") (pinfunction "K_3") (pintype "passive"))
      (node (ref "DS21") (pin "4") (pinfunction "K_4") (pintype "passive"))
      (node (ref "R56") (pin "2") (pinfunction "2_2") (pintype "passive"))
    )
    (net (code "65") (name "Net-(DS22-K-Pad1)") (class "Default")
      (node (ref "DS22") (pin "1") (pinfunction "K_1") (pintype "passive"))
      (node (ref "DS22") (pin "3") (pinfunction "K_3") (pintype "passive"))
      (node (ref "DS22") (pin "4") (pinfunction "K_4") (pintype "passive"))
      (node (ref "R57") (pin "2") (pinfunction "2_2") (pintype "passive"))
    )
    (net (code "66") (name "Net-(DS23-K-Pad1)") (class "Default")
      (node (ref "DS23") (pin "1") (pinfunction "K_1") (pintype "passive"))
      (node (ref "DS23") (pin "3") (pinfunction "K_3") (pintype "passive"))
      (node (ref "DS23") (pin "4") (pinfunction "K_4") (pintype "passive"))
      (node (ref "R68") (pin "2") (pinfunction "2_2") (pintype "passive"))
    )
    (net (code "67") (name "Net-(DS24-K-Pad1)") (class "Default")
      (node (ref "DS24") (pin "1") (pinfunction "K_1") (pintype "passive"))
      (node (ref "DS24") (pin "3") (pinfunction "K_3") (pintype "passive"))
      (node (ref "DS24") (pin "4") (pinfunction "K_4") (pintype "passive"))
      (node (ref "R69") (pin "2") (pinfunction "2_2") (pintype "passive"))
    )
    (net (code "68") (name "Net-(DS25-K-Pad1)") (class "Default")
      (node (ref "DS25") (pin "1") (pinfunction "K_1") (pintype "passive"))
      (node (ref "DS25") (pin "3") (pinfunction "K_3") (pintype "passive"))
      (node (ref "DS25") (pin "4") (pinfunction "K_4") (pintype "passive"))
      (node (ref "R88") (pin "2") (pinfunction "2_2") (pintype "passive"))
    )
    (net (code "69") (name "Net-(DS26-K-Pad1)") (class "Default")
      (node (ref "DS26") (pin "1") (pinfunction "K_1") (pintype "passive"))
      (node (ref "DS26") (pin "3") (pinfunction "K_3") (pintype "passive"))
      (node (ref "DS26") (pin "4") (pinfunction "K_4") (pintype "passive"))
      (node (ref "R89") (pin "2") (pinfunction "2_2") (pintype "passive"))
    )
    (net (code "70") (name "Net-(DS27-K-Pad1)") (class "Default")
      (node (ref "DS27") (pin "1") (pinfunction "K_1") (pintype "passive"))
      (node (ref "DS27") (pin "3") (pinfunction "K_3") (pintype "passive"))
      (node (ref "DS27") (pin "4") (pinfunction "K_4") (pintype "passive"))
      (node (ref "R100") (pin "2") (pinfunction "2_2") (pintype "passive"))
    )
    (net (code "71") (name "Net-(DS28-K-Pad1)") (class "Default")
      (node (ref "DS28") (pin "1") (pinfunction "K_1") (pintype "passive"))
      (node (ref "DS28") (pin "3") (pinfunction "K_3") (pintype "passive"))
      (node (ref "DS28") (pin "4") (pinfunction "K_4") (pintype "passive"))
      (node (ref "R101") (pin "2") (pinfunction "2_2") (pintype "passive"))
    )
    (net (code "72") (name "Net-(DS29-K-Pad1)") (class "Default")
      (node (ref "DS29") (pin "1") (pinfunction "K_1") (pintype "passive"))
      (node (ref "DS29") (pin "3") (pinfunction "K_3") (pintype "passive"))
      (node (ref "DS29") (pin "4") (pinfunction "K_4") (pintype "passive"))
      (node (ref "R90") (pin "2") (pinfunction "2_2") (pintype "passive"))
    )
    (net (code "73") (name "Net-(DS30-K-Pad1)") (class "Default")
      (node (ref "DS30") (pin "1") (pinfunction "K_1") (pintype "passive"))
      (node (ref "DS30") (pin "3") (pinfunction "K_3") (pintype "passive"))
      (node (ref "DS30") (pin "4") (pinfunction "K_4") (pintype "passive"))
      (node (ref "R91") (pin "2") (pinfunction "2_2") (pintype "passive"))
    )
    (net (code "74") (name "Net-(DS31-K-Pad1)") (class "Default")
      (node (ref "DS31") (pin "1") (pinfunction "K_1") (pintype "passive"))
      (node (ref "DS31") (pin "3") (pinfunction "K_3") (pintype "passive"))
      (node (ref "DS31") (pin "4") (pinfunction "K_4") (pintype "passive"))
      (node (ref "R102") (pin "2") (pinfunction "2_2") (pintype "passive"))
    )
    (net (code "75") (name "Net-(DS32-K-Pad1)") (class "Default")
      (node (ref "DS32") (pin "1") (pinfunction "K_1") (pintype "passive"))
      (node (ref "DS32") (pin "3") (pinfunction "K_3") (pintype "passive"))
      (node (ref "DS32") (pin "4") (pinfunction "K_4") (pintype "passive"))
      (node (ref "R103") (pin "2") (pinfunction "2_2") (pintype "passive"))
    )
    (net (code "76") (name "Net-(DS33-K-Pad1)") (class "Default")
      (node (ref "DS33") (pin "1") (pinfunction "K_1") (pintype "passive"))
      (node (ref "DS33") (pin "3") (pinfunction "K_3") (pintype "passive"))
      (node (ref "DS33") (pin "4") (pinfunction "K_4") (pintype "passive"))
      (node (ref "R92") (pin "2") (pinfunction "2_2") (pintype "passive"))
    )
    (net (code "77") (name "Net-(DS34-K-Pad1)") (class "Default")
      (node (ref "DS34") (pin "1") (pinfunction "K_1") (pintype "passive"))
      (node (ref "DS34") (pin "3") (pinfunction "K_3") (pintype "passive"))
      (node (ref "DS34") (pin "4") (pinfunction "K_4") (pintype "passive"))
      (node (ref "R93") (pin "2") (pinfunction "2_2") (pintype "passive"))
    )
    (net (code "78") (name "Net-(DS35-K-Pad1)") (class "Default")
      (node (ref "DS35") (pin "1") (pinfunction "K_1") (pintype "passive"))
      (node (ref "DS35") (pin "3") (pinfunction "K_3") (pintype "passive"))
      (node (ref "DS35") (pin "4") (pinfunction "K_4") (pintype "passive"))
      (node (ref "R104") (pin "2") (pinfunction "2_2") (pintype "passive"))
    )
    (net (code "79") (name "Net-(DS36-K-Pad1)") (class "Default")
      (node (ref "DS36") (pin "1") (pinfunction "K_1") (pintype "passive"))
      (node (ref "DS36") (pin "3") (pinfunction "K_3") (pintype "passive"))
      (node (ref "DS36") (pin "4") (pinfunction "K_4") (pintype "passive"))
      (node (ref "R105") (pin "2") (pinfunction "2_2") (pintype "passive"))
    )
    (net (code "80") (name "Net-(DS37-K-Pad1)") (class "Default")
      (node (ref "DS37") (pin "1") (pinfunction "K_1") (pintype "passive"))
      (node (ref "DS37") (pin "3") (pinfunction "K_3") (pintype "passive"))
      (node (ref "DS37") (pin "4") (pinfunction "K_4") (pintype "passive"))
      (node (ref "R94") (pin "2") (pinfunction "2_2") (pintype "passive"))
    )
    (net (code "81") (name "Net-(DS38-K-Pad1)") (class "Default")
      (node (ref "DS38") (pin "1") (pinfunction "K_1") (pintype "passive"))
      (node (ref "DS38") (pin "3") (pinfunction "K_3") (pintype "passive"))
      (node (ref "DS38") (pin "4") (pinfunction "K_4") (pintype "passive"))
      (node (ref "R95") (pin "2") (pinfunction "2_2") (pintype "passive"))
    )
    (net (code "82") (name "Net-(DS39-K-Pad1)") (class "Default")
      (node (ref "DS39") (pin "1") (pinfunction "K_1") (pintype "passive"))
      (node (ref "DS39") (pin "3") (pinfunction "K_3") (pintype "passive"))
      (node (ref "DS39") (pin "4") (pinfunction "K_4") (pintype "passive"))
      (node (ref "R106") (pin "2") (pinfunction "2_2") (pintype "passive"))
    )
    (net (code "83") (name "Net-(DS40-K-Pad1)") (class "Default")
      (node (ref "DS40") (pin "1") (pinfunction "K_1") (pintype "passive"))
      (node (ref "DS40") (pin "3") (pinfunction "K_3") (pintype "passive"))
      (node (ref "DS40") (pin "4") (pinfunction "K_4") (pintype "passive"))
      (node (ref "R107") (pin "2") (pinfunction "2_2") (pintype "passive"))
    )
    (net (code "84") (name "Net-(DS41-K-Pad1)") (class "Default")
      (node (ref "DS41") (pin "1") (pinfunction "K_1") (pintype "passive"))
      (node (ref "DS41") (pin "3") (pinfunction "K_3") (pintype "passive"))
      (node (ref "DS41") (pin "4") (pinfunction "K_4") (pintype "passive"))
      (node (ref "R96") (pin "2") (pinfunction "2_2") (pintype "passive"))
    )
    (net (code "85") (name "Net-(DS42-K-Pad1)") (class "Default")
      (node (ref "DS42") (pin "1") (pinfunction "K_1") (pintype "passive"))
      (node (ref "DS42") (pin "3") (pinfunction "K_3") (pintype "passive"))
      (node (ref "DS42") (pin "4") (pinfunction "K_4") (pintype "passive"))
      (node (ref "R97") (pin "2") (pinfunction "2_2") (pintype "passive"))
    )
    (net (code "86") (name "Net-(DS43-K-Pad1)") (class "Default")
      (node (ref "DS43") (pin "1") (pinfunction "K_1") (pintype "passive"))
      (node (ref "DS43") (pin "3") (pinfunction "K_3") (pintype "passive"))
      (node (ref "DS43") (pin "4") (pinfunction "K_4") (pintype "passive"))
      (node (ref "R108") (pin "2") (pinfunction "2_2") (pintype "passive"))
    )
    (net (code "87") (name "Net-(DS44-K-Pad1)") (class "Default")
      (node (ref "DS44") (pin "1") (pinfunction "K_1") (pintype "passive"))
      (node (ref "DS44") (pin "3") (pinfunction "K_3") (pintype "passive"))
      (node (ref "DS44") (pin "4") (pinfunction "K_4") (pintype "passive"))
      (node (ref "R109") (pin "2") (pinfunction "2_2") (pintype "passive"))
    )
    (net (code "88") (name "Net-(DS45-K-Pad1)") (class "Default")
      (node (ref "DS45") (pin "1") (pinfunction "K_1") (pintype "passive"))
      (node (ref "DS45") (pin "3") (pinfunction "K_3") (pintype "passive"))
      (node (ref "DS45") (pin "4") (pinfunction "K_4") (pintype "passive"))
      (node (ref "R98") (pin "2") (pinfunction "2_2") (pintype "passive"))
    )
    (net (code "89") (name "Net-(DS46-K-Pad1)") (class "Default")
      (node (ref "DS46") (pin "1") (pinfunction "K_1") (pintype "passive"))
      (node (ref "DS46") (pin "3") (pinfunction "K_3") (pintype "passive"))
      (node (ref "DS46") (pin "4") (pinfunction "K_4") (pintype "passive"))
      (node (ref "R99") (pin "2") (pinfunction "2_2") (pintype "passive"))
    )
    (net (code "90") (name "Net-(DS47-K-Pad1)") (class "Default")
      (node (ref "DS47") (pin "1") (pinfunction "K_1") (pintype "passive"))
      (node (ref "DS47") (pin "3") (pinfunction "K_3") (pintype "passive"))
      (node (ref "DS47") (pin "4") (pinfunction "K_4") (pintype "passive"))
      (node (ref "R110") (pin "2") (pinfunction "2_2") (pintype "passive"))
    )
    (net (code "91") (name "Net-(DS48-K-Pad1)") (class "Default")
      (node (ref "DS48") (pin "1") (pinfunction "K_1") (pintype "passive"))
      (node (ref "DS48") (pin "3") (pinfunction "K_3") (pintype "passive"))
      (node (ref "DS48") (pin "4") (pinfunction "K_4") (pintype "passive"))
      (node (ref "R111") (pin "2") (pinfunction "2_2") (pintype "passive"))
    )
    (net (code "92") (name "Net-(DS49-A)") (class "Default")
      (node (ref "DS49") (pin "1") (pinfunction "A_1") (pintype "passive"))
      (node (ref "Q1") (pin "4") (pinfunction "G_4") (pintype "passive"))
      (node (ref "R28") (pin "2") (pinfunction "2_2") (pintype "passive"))
    )
    (net (code "93") (name "Net-(DS50-A)") (class "Default")
      (node (ref "DS50") (pin "1") (pinfunction "A_1") (pintype "passive"))
      (node (ref "Q2") (pin "4") (pinfunction "G_4") (pintype "passive"))
      (node (ref "R40") (pin "2") (pinfunction "2_2") (pintype "passive"))
    )
    (net (code "94") (name "Net-(J2-.125_AMP-IN)") (class "Default")
      (node (ref "D1") (pin "A") (pinfunction "A_A") (pintype "passive"))
      (node (ref "J2") (pin "1") (pinfunction ".125_AMP-IN_1") (pintype "passive"))
      (node (ref "J6") (pin "1") (pinfunction ".125_AMP-IN_1") (pintype "passive"))
    )
    (net (code "95") (name "Net-(J3-.125_AMP-IN)") (class "Default")
      (node (ref "J3") (pin "1") (pinfunction ".125_AMP-IN_1") (pintype "passive"))
      (node (ref "J7") (pin "1") (pinfunction ".125_AMP-IN_1") (pintype "passive"))
      (node (ref "R5") (pin "2") (pinfunction "2_2") (pintype "passive"))
      (node (ref "U3") (pin "7") (pinfunction "CANH_7") (pintype "bidirectional"))
    )
    (net (code "96") (name "Net-(J4-.125_AMP-IN)") (class "Default")
      (node (ref "J4") (pin "1") (pinfunction ".125_AMP-IN_1") (pintype "passive"))
      (node (ref "J8") (pin "1") (pinfunction ".125_AMP-IN_1") (pintype "passive"))
      (node (ref "R5") (pin "1") (pinfunction "1_1") (pintype "passive"))
      (node (ref "U3") (pin "6") (pinfunction "CANL_6") (pintype "bidirectional"))
    )
    (net (code "97") (name "Net-(J9-.125_AMP-IN)") (class "Default")
      (node (ref "J9") (pin "1") (pinfunction ".125_AMP-IN_1") (pintype "passive"))
      (node (ref "R16") (pin "2") (pinfunction "2_2") (pintype "passive"))
      (node (ref "U10") (pin "5") (pinfunction "VOUT1_5") (pintype "output"))
    )
    (net (code "98") (name "Net-(J10-.125_AMP-IN)") (class "Default")
      (node (ref "J10") (pin "1") (pinfunction ".125_AMP-IN_1") (pintype "passive"))
      (node (ref "U10") (pin "8") (pinfunction "VOUT2_8") (pintype "output"))
    )
    (net (code "99") (name "Net-(J11-.125_AMP-IN)") (class "Default")
      (node (ref "J11") (pin "1") (pinfunction ".125_AMP-IN_1") (pintype "passive"))
      (node (ref "R128") (pin "1") (pinfunction "1_1") (pintype "passive"))
    )
    (net (code "100") (name "Net-(Q1-D-Pad5)") (class "Default")
      (node (ref "Q1") (pin "5") (pinfunction "D_5") (pintype "passive"))
      (node (ref "Q1") (pin "6") (pinfunction "D_6") (pintype "passive"))
      (node (ref "Q1") (pin "7") (pinfunction "D_7") (pintype "passive"))
      (node (ref "Q1") (pin "8") (pinfunction "D_8") (pintype "passive"))
      (node (ref "R46") (pin "1") (pinfunction "1_1") (pintype "passive"))
      (node (ref "R47") (pin "1") (pinfunction "1_1") (pintype "passive"))
      (node (ref "R48") (pin "1") (pinfunction "1_1") (pintype "passive"))
      (node (ref "R49") (pin "1") (pinfunction "1_1") (pintype "passive"))
      (node (ref "R50") (pin "1") (pinfunction "1_1") (pintype "passive"))
      (node (ref "R51") (pin "1") (pinfunction "1_1") (pintype "passive"))
      (node (ref "R52") (pin "1") (pinfunction "1_1") (pintype "passive"))
      (node (ref "R53") (pin "1") (pinfunction "1_1") (pintype "passive"))
      (node (ref "R54") (pin "1") (pinfunction "1_1") (pintype "passive"))
      (node (ref "R55") (pin "1") (pinfunction "1_1") (pintype "passive"))
      (node (ref "R56") (pin "1") (pinfunction "1_1") (pintype "passive"))
      (node (ref "R57") (pin "1") (pinfunction "1_1") (pintype "passive"))
      (node (ref "R88") (pin "1") (pinfunction "1_1") (pintype "passive"))
      (node (ref "R89") (pin "1") (pinfunction "1_1") (pintype "passive"))
      (node (ref "R90") (pin "1") (pinfunction "1_1") (pintype "passive"))
      (node (ref "R91") (pin "1") (pinfunction "1_1") (pintype "passive"))
      (node (ref "R92") (pin "1") (pinfunction "1_1") (pintype "passive"))
      (node (ref "R93") (pin "1") (pinfunction "1_1") (pintype "passive"))
      (node (ref "R94") (pin "1") (pinfunction "1_1") (pintype "passive"))
      (node (ref "R95") (pin "1") (pinfunction "1_1") (pintype "passive"))
      (node (ref "R96") (pin "1") (pinfunction "1_1") (pintype "passive"))
      (node (ref "R97") (pin "1") (pinfunction "1_1") (pintype "passive"))
      (node (ref "R98") (pin "1") (pinfunction "1_1") (pintype "passive"))
      (node (ref "R99") (pin "1") (pinfunction "1_1") (pintype "passive"))
    )
    (net (code "101") (name "Net-(Q2-D-Pad5)") (class "Default")
      (node (ref "Q2") (pin "5") (pinfunction "D_5") (pintype "passive"))
      (node (ref "Q2") (pin "6") (pinfunction "D_6") (pintype "passive"))
      (node (ref "Q2") (pin "7") (pinfunction "D_7") (pintype "passive"))
      (node (ref "Q2") (pin "8") (pinfunction "D_8") (pintype "passive"))
      (node (ref "R100") (pin "1") (pinfunction "1_1") (pintype "passive"))
      (node (ref "R101") (pin "1") (pinfunction "1_1") (pintype "passive"))
      (node (ref "R102") (pin "1") (pinfunction "1_1") (pintype "passive"))
      (node (ref "R103") (pin "1") (pinfunction "1_1") (pintype "passive"))
      (node (ref "R104") (pin "1") (pinfunction "1_1") (pintype "passive"))
      (node (ref "R105") (pin "1") (pinfunction "1_1") (pintype "passive"))
      (node (ref "R106") (pin "1") (pinfunction "1_1") (pintype "passive"))
      (node (ref "R107") (pin "1") (pinfunction "1_1") (pintype "passive"))
      (node (ref "R108") (pin "1") (pinfunction "1_1") (pintype "passive"))
      (node (ref "R109") (pin "1") (pinfunction "1_1") (pintype "passive"))
      (node (ref "R110") (pin "1") (pinfunction "1_1") (pintype "passive"))
      (node (ref "R111") (pin "1") (pinfunction "1_1") (pintype "passive"))
      (node (ref "R58") (pin "1") (pinfunction "1_1") (pintype "passive"))
      (node (ref "R59") (pin "1") (pinfunction "1_1") (pintype "passive"))
      (node (ref "R60") (pin "1") (pinfunction "1_1") (pintype "passive"))
      (node (ref "R61") (pin "1") (pinfunction "1_1") (pintype "passive"))
      (node (ref "R62") (pin "1") (pinfunction "1_1") (pintype "passive"))
      (node (ref "R63") (pin "1") (pinfunction "1_1") (pintype "passive"))
      (node (ref "R64") (pin "1") (pinfunction "1_1") (pintype "passive"))
      (node (ref "R65") (pin "1") (pinfunction "1_1") (pintype "passive"))
      (node (ref "R66") (pin "1") (pinfunction "1_1") (pintype "passive"))
      (node (ref "R67") (pin "1") (pinfunction "1_1") (pintype "passive"))
      (node (ref "R68") (pin "1") (pinfunction "1_1") (pintype "passive"))
      (node (ref "R69") (pin "1") (pinfunction "1_1") (pintype "passive"))
    )
    (net (code "102") (name "Net-(R128-Pad2)") (class "Default")
      (node (ref "R128") (pin "2") (pinfunction "2_2") (pintype "passive"))
      (node (ref "R22") (pin "1") (pinfunction "1_1") (pintype "passive"))
      (node (ref "U12") (pin "2") (pinfunction "2_2") (pintype "passive"))
      (node (ref "U12") (pin "3") (pinfunction "3_3") (pintype "passive"))
    )
    (net (code "103") (name "Net-(U1-~{HOLD})") (class "Default")
      (node (ref "R2") (pin "2") (pinfunction "2_2") (pintype "passive"))
      (node (ref "U1") (pin "1") (pinfunction "~{HOLD}_1") (pintype "input"))
      (node (ref "U4") (pin "1") (pinfunction "~{HOLD}_1") (pintype "input"))
      (node (ref "U8") (pin "1") (pinfunction "~{HOLD}_1") (pintype "input"))
      (node (ref "U9") (pin "1") (pinfunction "~{HOLD}_1") (pintype "input"))
    )
    (net (code "104") (name "Net-(U2-OSC1{slash}CLKIN)") (class "Default")
      (node (ref "C20") (pin "1") (pinfunction "1_1") (pintype "passive"))
      (node (ref "U2") (pin "49") (pinfunction "OSC1/CLKIN_49") (pintype "input"))
      (node (ref "Y1") (pin "1") (pinfunction "OSC1_1") (pintype "passive"))
    )
    (net (code "105") (name "Net-(U5-AOUTR)") (class "Default")
      (node (ref "C15") (pin "1") (pinfunction "1_1") (pintype "passive"))
      (node (ref "U5") (pin "10") (pinfunction "AOUTR_10") (pintype "passive"))
    )
    (net (code "106") (name "Net-(U5-FILT+)") (class "Default")
      (node (ref "C14") (pin "1") (pinfunction "1_1") (pintype "passive"))
      (node (ref "U5") (pin "6") (pinfunction "FILT+_6") (pintype "passive"))
    )
    (net (code "107") (name "Net-(U5-VQ)") (class "Default")
      (node (ref "C6") (pin "1") (pinfunction "1_1") (pintype "passive"))
      (node (ref "C9") (pin "1") (pinfunction "1_1") (pintype "passive"))
      (node (ref "U5") (pin "5") (pinfunction "VQ_5") (pintype "passive"))
    )
    (net (code "108") (name "Net-(U6-CBOOST)") (class "Default")
      (node (ref "C12") (pin "1") (pinfunction "1_1") (pintype "passive"))
      (node (ref "U6") (pin "3") (pinfunction "CBOOST_3") (pintype "power_in"))
    )
    (net (code "109") (name "Net-(U6-FB)") (class "Default")
      (node (ref "R7") (pin "2") (pinfunction "2_2") (pintype "passive"))
      (node (ref "R9") (pin "1") (pinfunction "1_1") (pintype "passive"))
      (node (ref "U6") (pin "6") (pinfunction "FB_6") (pintype "input"))
    )
    (net (code "110") (name "Net-(U6-~{ON}{slash}OFF)") (class "Default")
      (node (ref "R130") (pin "2") (pinfunction "2_2") (pintype "passive"))
      (node (ref "U6") (pin "7") (pinfunction "~{ON}/OFF_7") (pintype "input"))
    )
    (net (code "111") (name "Net-(U10-BYP)") (class "Default")
      (node (ref "C28") (pin "1") (pinfunction "1_1") (pintype "passive"))
      (node (ref "U10") (pin "2") (pinfunction "BYP_2") (pintype "passive"))
      (node (ref "U10") (pin "3") (pinfunction "IN+_3") (pintype "input"))
    )
    (net (code "112") (name "Net-(U10-IN-)") (class "Default")
      (node (ref "R13") (pin "2") (pinfunction "2_2") (pintype "passive"))
      (node (ref "R16") (pin "1") (pinfunction "1_1") (pintype "passive"))
      (node (ref "U10") (pin "4") (pinfunction "IN-_4") (pintype "input"))
    )
    (net (code "113") (name "Net-(U11-CBOOST)") (class "Default")
      (node (ref "C26") (pin "1") (pinfunction "1_1") (pintype "passive"))
      (node (ref "U11") (pin "3") (pinfunction "CBOOST_3") (pintype "power_in"))
    )
    (net (code "114") (name "Net-(U11-FB)") (class "Default")
      (node (ref "R17") (pin "2") (pinfunction "2_2") (pintype "passive"))
      (node (ref "R18") (pin "1") (pinfunction "1_1") (pintype "passive"))
      (node (ref "U11") (pin "6") (pinfunction "FB_6") (pintype "input"))
    )
    (net (code "115") (name "Net-(U11-~{ON}{slash}OFF)") (class "Default")
      (node (ref "R20") (pin "2") (pinfunction "2_2") (pintype "passive"))
      (node (ref "U11") (pin "7") (pinfunction "~{ON}/OFF_7") (pintype "input"))
    )
    (net (code "116") (name "Net-(U13-A)") (class "Default")
      (node (ref "R29") (pin "1") (pinfunction "1_1") (pintype "passive"))
      (node (ref "R8") (pin "1") (pinfunction "1_1") (pintype "passive"))
      (node (ref "U13") (pin "2") (pinfunction "A_2") (pintype "input"))
      (node (ref "U2") (pin "50") (pinfunction "OSC2/CLK0/RC15_50") (pintype "bidirectional"))
    )
    (net (code "117") (name "Net-(Y1-OSC2)") (class "Default")
      (node (ref "C16") (pin "1") (pinfunction "1_1") (pintype "passive"))
      (node (ref "R8") (pin "2") (pinfunction "2_2") (pintype "passive"))
      (node (ref "Y1") (pin "2") (pinfunction "OSC2_2") (pintype "passive"))
    )
    (net (code "118") (name "VCC") (class "Default")
      (node (ref "C1") (pin "1") (pinfunction "1_1") (pintype "passive"))
      (node (ref "C11") (pin "1") (pinfunction "1_1") (pintype "passive"))
      (node (ref "C17") (pin "1") (pinfunction "1_1") (pintype "passive"))
      (node (ref "C19") (pin "1") (pinfunction "1_1") (pintype "passive"))
      (node (ref "C2") (pin "1") (pinfunction "1_1") (pintype "passive"))
      (node (ref "C21") (pin "1") (pinfunction "1_1") (pintype "passive"))
      (node (ref "C23") (pin "1") (pinfunction "1_1") (pintype "passive"))
      (node (ref "C3") (pin "1") (pinfunction "1_1") (pintype "passive"))
      (node (ref "C33") (pin "1") (pinfunction "1_1") (pintype "passive"))
      (node (ref "C4") (pin "1") (pinfunction "1_1") (pintype "passive"))
      (node (ref "C42") (pin "1") (pinfunction "1_1") (pintype "passive"))
      (node (ref "C8") (pin "1") (pinfunction "1_1") (pintype "passive"))
      (node (ref "J14") (pin "2") (pinfunction "2_2") (pintype "passive"))
      (node (ref "R1") (pin "1") (pinfunction "1_1") (pintype "passive"))
      (node (ref "R10") (pin "2") (pinfunction "2_2") (pintype "passive"))
      (node (ref "R112") (pin "2") (pinfunction "2_2") (pintype "passive"))
      (node (ref "R129") (pin "2") (pinfunction "2_2") (pintype "passive"))
      (node (ref "R14") (pin "2") (pinfunction "2_2") (pintype "passive"))
      (node (ref "R15") (pin "2") (pinfunction "2_2") (pintype "passive"))
      (node (ref "R19") (pin "2") (pinfunction "2_2") (pintype "passive"))
      (node (ref "R2") (pin "1") (pinfunction "1_1") (pintype "passive"))
      (node (ref "R21") (pin "2") (pinfunction "2_2") (pintype "passive"))
      (node (ref "R23") (pin "2") (pinfunction "2_2") (pintype "passive"))
      (node (ref "R26") (pin "2") (pinfunction "2_2") (pintype "passive"))
      (node (ref "R27") (pin "2") (pinfunction "2_2") (pintype "passive"))
      (node (ref "R3") (pin "2") (pinfunction "2_2") (pintype "passive"))
      (node (ref "R30") (pin "2") (pinfunction "2_2") (pintype "passive"))
      (node (ref "R4") (pin "2") (pinfunction "2_2") (pintype "passive"))
      (node (ref "R6") (pin "2") (pinfunction "2_2") (pintype "passive"))
      (node (ref "U1") (pin "2") (pinfunction "VCC_2") (pintype "power_in"))
      (node (ref "U13") (pin "5") (pinfunction "VCC_5") (pintype "power_in"))
      (node (ref "U14") (pin "6") (pinfunction "VDD_6") (pintype "power_in"))
      (node (ref "U14") (pin "7") (pinfunction "REGIN_7") (pintype "input"))
      (node (ref "U2") (pin "12") (pinfunction "VDD_12") (pintype "power_in"))
      (node (ref "U2") (pin "25") (pinfunction "AVDD_25") (pintype "power_in"))
      (node (ref "U2") (pin "32") (pinfunction "VDD_32") (pintype "power_in"))
      (node (ref "U2") (pin "48") (pinfunction "VDD_48") (pintype "power_in"))
      (node (ref "U2") (pin "71") (pinfunction "VDD_71") (pintype "power_in"))
      (node (ref "U3") (pin "3") (pinfunction "VCC_3") (pintype "power_in"))
      (node (ref "U4") (pin "2") (pinfunction "VCC_2") (pintype "power_in"))
      (node (ref "U5") (pin "9") (pinfunction "VA_9") (pintype "passive"))
      (node (ref "U7") (pin "3") (pinfunction "OUT_3") (pintype "power_in"))
      (node (ref "U8") (pin "2") (pinfunction "VCC_2") (pintype "power_in"))
      (node (ref "U9") (pin "2") (pinfunction "VCC_2") (pintype "power_in"))
    )
    (net (code "119") (name "unconnected-(D2-NC-Pad1)") (class "Default")
      (node (ref "D2") (pin "1") (pinfunction "NC_1") (pintype "passive"))
    )
    (net (code "120") (name "unconnected-(D7-NC-Pad1)") (class "Default")
      (node (ref "D7") (pin "1") (pinfunction "NC_1") (pintype "passive"))
    )
    (net (code "121") (name "unconnected-(J13-SHLD-Pad5)") (class "Default")
      (node (ref "J13") (pin "5") (pinfunction "SHLD_5") (pintype "passive"))
    )
    (net (code "122") (name "unconnected-(J13-SHLD-Pad6)") (class "Default")
      (node (ref "J13") (pin "6") (pinfunction "SHLD_6") (pintype "passive"))
    )
    (net (code "123") (name "unconnected-(J14-Pad6)") (class "Default")
      (node (ref "J14") (pin "6") (pinfunction "6_6") (pintype "passive"))
    )
    (net (code "124") (name "unconnected-(U2-AN3{slash}CN5{slash}RB3-Pad17)") (class "Default")
      (node (ref "U2") (pin "17") (pinfunction "AN3/CN5/RB3_17") (pintype "bidirectional"))
    )
    (net (code "125") (name "unconnected-(U2-AN4{slash}IC7{slash}CN6{slash}RB4-Pad16)") (class "Default")
      (node (ref "U2") (pin "16") (pinfunction "AN4/IC7/CN6/RB4_16") (pintype "bidirectional"))
    )
    (net (code "126") (name "unconnected-(U2-AN5{slash}IC8{slash}CN7{slash}RB5-Pad15)") (class "Default")
      (node (ref "U2") (pin "15") (pinfunction "AN5/IC8/CN7/RB5_15") (pintype "bidirectional"))
    )
    (net (code "127") (name "unconnected-(U2-AN8{slash}RB8-Pad27)") (class "Default")
      (node (ref "U2") (pin "27") (pinfunction "AN8/RB8_27") (pintype "bidirectional"))
    )
    (net (code "128") (name "unconnected-(U2-AN9{slash}RB9-Pad28)") (class "Default")
      (node (ref "U2") (pin "28") (pinfunction "AN9/RB9_28") (pintype "bidirectional"))
    )
    (net (code "129") (name "unconnected-(U2-AN10{slash}RB10-Pad29)") (class "Default")
      (node (ref "U2") (pin "29") (pinfunction "AN10/RB10_29") (pintype "bidirectional"))
    )
    (net (code "130") (name "unconnected-(U2-AN11{slash}RB11-Pad30)") (class "Default")
      (node (ref "U2") (pin "30") (pinfunction "AN11/RB11_30") (pintype "bidirectional"))
    )
    (net (code "131") (name "unconnected-(U2-AN12{slash}RB12-Pad33)") (class "Default")
      (node (ref "U2") (pin "33") (pinfunction "AN12/RB12_33") (pintype "bidirectional"))
    )
    (net (code "132") (name "unconnected-(U2-EMUC1{slash}SOSCO{slash}T1CK{slash}CN0{slash}RC14-Pad60)") (class "Default")
      (node (ref "U2") (pin "60") (pinfunction "EMUC1/SOSCO/T1CK/CN0/RC14_60") (pintype "bidirectional"))
    )
    (net (code "133") (name "unconnected-(U2-EMUD1{slash}SOSCI{slash}CN1{slash}RC13-Pad59)") (class "Default")
      (node (ref "U2") (pin "59") (pinfunction "EMUD1/SOSCI/CN1/RC13_59") (pintype "bidirectional"))
    )
    (net (code "134") (name "unconnected-(U2-IC1{slash}RD8-Pad54)") (class "Default")
      (node (ref "U2") (pin "54") (pinfunction "IC1/RD8_54") (pintype "bidirectional"))
    )
    (net (code "135") (name "unconnected-(U2-IC2{slash}RD9-Pad55)") (class "Default")
      (node (ref "U2") (pin "55") (pinfunction "IC2/RD9_55") (pintype "bidirectional"))
    )
    (net (code "136") (name "unconnected-(U2-IC3{slash}RD10-Pad56)") (class "Default")
      (node (ref "U2") (pin "56") (pinfunction "IC3/RD10_56") (pintype "bidirectional"))
    )
    (net (code "137") (name "unconnected-(U2-IC4{slash}RD11-Pad57)") (class "Default")
      (node (ref "U2") (pin "57") (pinfunction "IC4/RD11_57") (pintype "bidirectional"))
    )
    (net (code "138") (name "unconnected-(U2-IC5{slash}RD12-Pad64)") (class "Default")
      (node (ref "U2") (pin "64") (pinfunction "IC5/RD12_64") (pintype "bidirectional"))
    )
    (net (code "139") (name "unconnected-(U2-IC6{slash}CN19{slash}RD13-Pad65)") (class "Default")
      (node (ref "U2") (pin "65") (pinfunction "IC6/CN19/RD13_65") (pintype "bidirectional"))
    )
    (net (code "140") (name "unconnected-(U2-IC7{slash}CN20{slash}RD14-Pad37)") (class "Default")
      (node (ref "U2") (pin "37") (pinfunction "IC7/CN20/RD14_37") (pintype "bidirectional"))
    )
    (net (code "141") (name "unconnected-(U2-IC8{slash}CN21{slash}RD15-Pad38)") (class "Default")
      (node (ref "U2") (pin "38") (pinfunction "IC8/CN21/RD15_38") (pintype "bidirectional"))
    )
    (net (code "142") (name "unconnected-(U2-OC3{slash}RD2-Pad62)") (class "Default")
      (node (ref "U2") (pin "62") (pinfunction "OC3/RD2_62") (pintype "bidirectional"))
    )
    (net (code "143") (name "unconnected-(U2-OC4{slash}RD3-Pad63)") (class "Default")
      (node (ref "U2") (pin "63") (pinfunction "OC4/RD3_63") (pintype "bidirectional"))
    )
    (net (code "144") (name "unconnected-(U2-OC5{slash}CN13{slash}RD4-Pad66)") (class "Default")
      (node (ref "U2") (pin "66") (pinfunction "OC5/CN13/RD4_66") (pintype "bidirectional"))
    )
    (net (code "145") (name "unconnected-(U2-OC6{slash}CN14{slash}RD5-Pad67)") (class "Default")
      (node (ref "U2") (pin "67") (pinfunction "OC6/CN14/RD5_67") (pintype "bidirectional"))
    )
    (net (code "146") (name "unconnected-(U2-OC7{slash}CN15{slash}RD6-Pad68)") (class "Default")
      (node (ref "U2") (pin "68") (pinfunction "OC7/CN15/RD6_68") (pintype "bidirectional"))
    )
    (net (code "147") (name "unconnected-(U2-PGC{slash}EMUC{slash}AN6{slash}OCFA{slash}RB6-Pad21)") (class "Default")
      (node (ref "U2") (pin "21") (pinfunction "PGC/EMUC/AN6/OCFA/RB6_21") (pintype "bidirectional"))
    )
    (net (code "148") (name "unconnected-(U2-PGD{slash}EMUD{slash}AN7{slash}RB7-Pad22)") (class "Default")
      (node (ref "U2") (pin "22") (pinfunction "PGD/EMUD/AN7/RB7_22") (pintype "bidirectional"))
    )
    (net (code "149") (name "unconnected-(U2-SCK2{slash}CN8{slash}RG6-Pad6)") (class "Default")
      (node (ref "U2") (pin "6") (pinfunction "SCK2/CN8/RG6_6") (pintype "bidirectional"))
    )
    (net (code "150") (name "unconnected-(U2-SCL{slash}RG2-Pad47)") (class "Default")
      (node (ref "U2") (pin "47") (pinfunction "SCL/RG2_47") (pintype "bidirectional"))
    )
    (net (code "151") (name "unconnected-(U2-SDI2{slash}CN9{slash}RG7-Pad7)") (class "Default")
      (node (ref "U2") (pin "7") (pinfunction "SDI2/CN9/RG7_7") (pintype "bidirectional"))
    )
    (net (code "152") (name "unconnected-(U2-SDO2{slash}CN10{slash}RG8-Pad8)") (class "Default")
      (node (ref "U2") (pin "8") (pinfunction "SDO2/CN10/RG8_8") (pintype "bidirectional"))
    )
    (net (code "153") (name "unconnected-(U2-T2CK{slash}RC1-Pad2)") (class "Default")
      (node (ref "U2") (pin "2") (pinfunction "T2CK/RC1_2") (pintype "bidirectional"))
    )
    (net (code "154") (name "unconnected-(U2-T3CK{slash}RC2-Pad3)") (class "Default")
      (node (ref "U2") (pin "3") (pinfunction "T3CK/RC2_3") (pintype "bidirectional"))
    )
    (net (code "155") (name "unconnected-(U2-U1RX{slash}RF2-Pad42)") (class "Default")
      (node (ref "U2") (pin "42") (pinfunction "U1RX/RF2_42") (pintype "bidirectional"))
    )
    (net (code "156") (name "unconnected-(U2-U1TX{slash}RF3-Pad41)") (class "Default")
      (node (ref "U2") (pin "41") (pinfunction "U1TX/RF3_41") (pintype "bidirectional"))
    )
    (net (code "157") (name "unconnected-(U2-~{SS2}{slash}CN11{slash}RG9-Pad10)") (class "Default")
      (node (ref "U2") (pin "10") (pinfunction "~{SS2}/CN11/RG9_10") (pintype "bidirectional"))
    )
    (net (code "158") (name "unconnected-(U3-VREF-Pad5)") (class "Default")
      (node (ref "U3") (pin "5") (pinfunction "VREF_5") (pintype "passive"))
    )
    (net (code "159") (name "unconnected-(U5-AOUTL-Pad7)") (class "Default")
      (node (ref "U5") (pin "7") (pinfunction "AOUTL_7") (pintype "passive"))
    )
    (net (code "160") (name "unconnected-(U6-NC-Pad5)") (class "Default")
      (node (ref "U6") (pin "5") (pinfunction "NC_5") (pintype "passive"))
    )
    (net (code "161") (name "unconnected-(U11-NC-Pad5)") (class "Default")
      (node (ref "U11") (pin "5") (pinfunction "NC_5") (pintype "passive"))
    )
    (net (code "162") (name "unconnected-(U12-Pad5)") (class "Default")
      (node (ref "U12") (pin "5") (pinfunction "5_5") (pintype "passive"))
    )
    (net (code "163") (name "unconnected-(U12-Pad6)") (class "Default")
      (node (ref "U12") (pin "6") (pinfunction "6_6") (pintype "passive"))
    )
    (net (code "164") (name "unconnected-(U14-CTS-Pad23)") (class "Default")
      (node (ref "U14") (pin "23") (pinfunction "CTS_23") (pintype "input"))
    )
    (net (code "165") (name "unconnected-(U14-DCD-Pad1)") (class "Default")
      (node (ref "U14") (pin "1") (pinfunction "DCD_1") (pintype "input"))
    )
    (net (code "166") (name "unconnected-(U14-DSR-Pad27)") (class "Default")
      (node (ref "U14") (pin "27") (pinfunction "DSR_27") (pintype "input"))
    )
    (net (code "167") (name "unconnected-(U14-DTR-Pad28)") (class "Default")
      (node (ref "U14") (pin "28") (pinfunction "DTR_28") (pintype "output"))
    )
    (net (code "168") (name "unconnected-(U14-RI-Pad2)") (class "Default")
      (node (ref "U14") (pin "2") (pinfunction "RI_2") (pintype "input"))
    )
    (net (code "169") (name "unconnected-(U14-RTS-Pad24)") (class "Default")
      (node (ref "U14") (pin "24") (pinfunction "RTS_24") (pintype "output"))
    )
    (net (code "170") (name "unconnected-(U14-SUSPEND-Pad12)") (class "Default")
      (node (ref "U14") (pin "12") (pinfunction "SUSPEND_12") (pintype "output"))
    )
    (net (code "171") (name "unconnected-(U14-~{SUSPEND}-Pad11)") (class "Default")
      (node (ref "U14") (pin "11") (pinfunction "~{SUSPEND}_11") (pintype "output"))
    )
  )
)
